# PLC-_-V2.net
KiCad netlist of a schematic drawn in Altium Designer
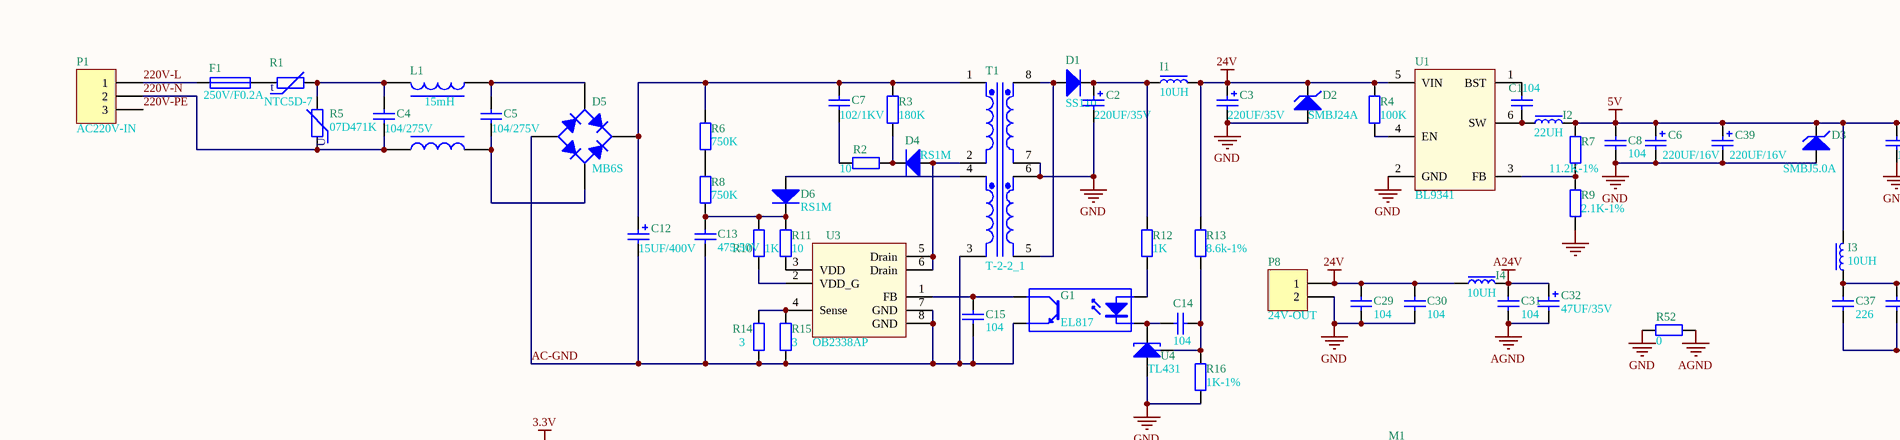
[diagram p0: PLC-无线通讯版-V2.SchDoc, top left]
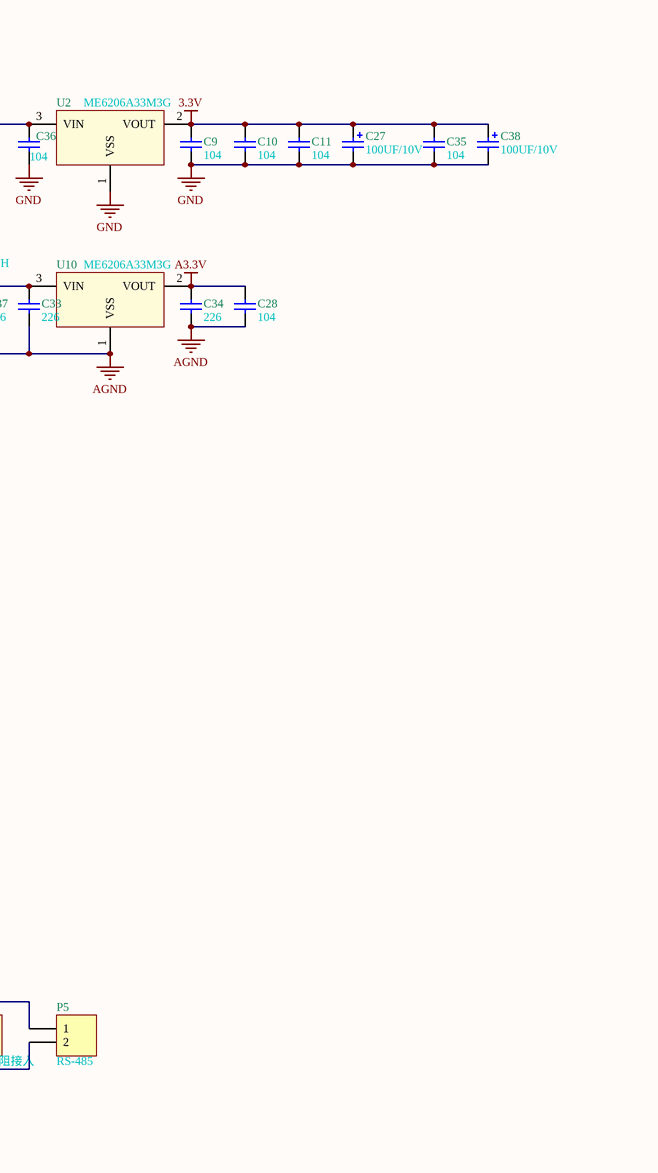
[diagram p1: PLC-无线通讯版-V2.SchDoc, top right]
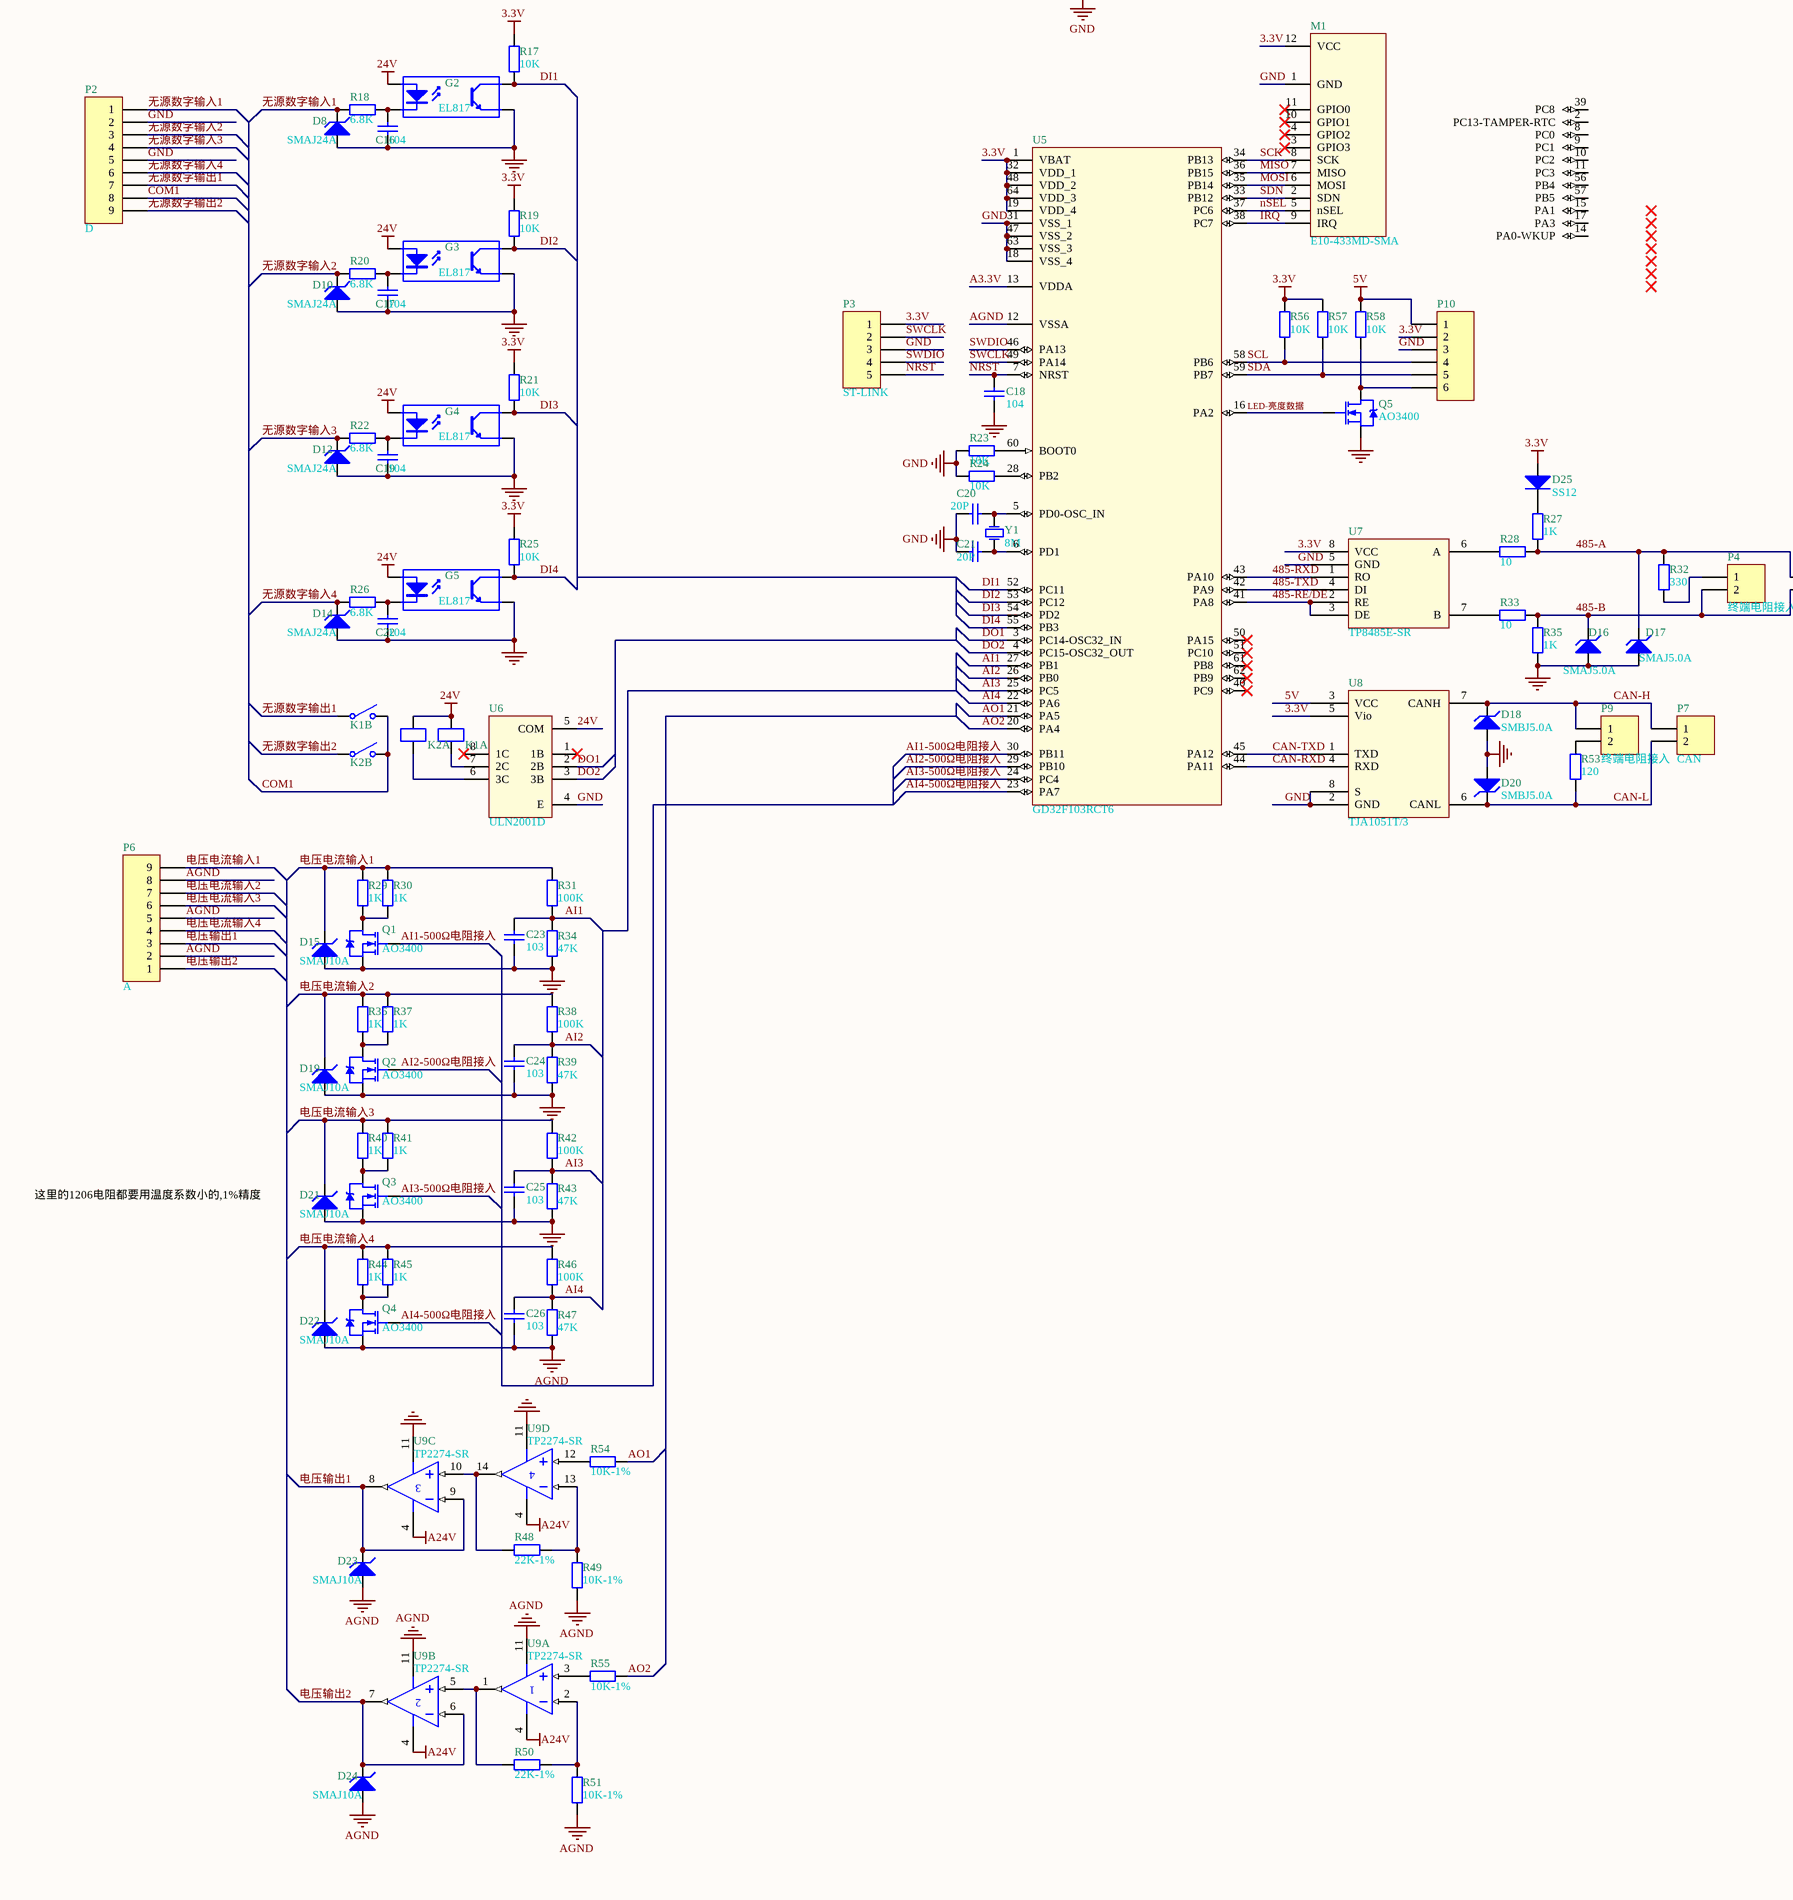
[diagram p2: PLC-无线通讯版-V2.SchDoc, bottom left]
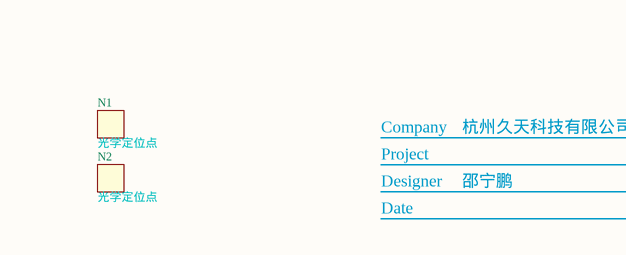
[diagram p3: PLC-无线通讯版-V2.SchDoc, bottom right]

(export (version "E")
  (design (tool "Eeschema 10.0.6"))
  (components
    (comp (ref "C1")
      (value "104")
      (footprint "C-0603")
      (description "Capacitor")
      (fields (field (name "PUBLISHER") "Altium Limited"))
      (libsource (lib "元件2.0") (part "Cap"))
    )
    (comp (ref "C2")
      (value "220UF/35V")
      (footprint "贴片固态电容8*10-M")
      (description "电解电容")
      (fields (field (name "PUBLISHER") "Altium Limited"))
      (libsource (lib "2电容-V1.0") (part "Cap Pol1"))
    )
    (comp (ref "C3")
      (value "220UF/35V")
      (footprint "贴片固态电容8*10-M")
      (description "电解电容")
      (fields (field (name "PUBLISHER") "Altium Limited"))
      (libsource (lib "2电容-V1.0") (part "Cap Pol1"))
    )
    (comp (ref "C4")
      (value "104/275V")
      (footprint "安规电容 脚距10")
      (description "Capacitor")
      (fields (field (name "PUBLISHER") "Altium Limited"))
      (libsource (lib "元件2.0") (part "Cap"))
    )
    (comp (ref "C5")
      (value "104/275V")
      (footprint "安规电容 脚距10")
      (description "Capacitor")
      (fields (field (name "PUBLISHER") "Altium Limited"))
      (libsource (lib "元件2.0") (part "Cap"))
    )
    (comp (ref "C6")
      (value "220UF/16V")
      (footprint "贴片固态电容6.3*7.7")
      (description "Polarized Capacitor (Radial)")
      (fields (field (name "PUBLISHER") "Altium Limited"))
      (libsource (lib "元件2.0") (part "Cap Pol1"))
    )
    (comp (ref "C7")
      (value "102/1KV")
      (footprint "C-1206-M")
      (description "0805")
      (fields (field (name "PUBLISHER") "Altium Limited"))
      (libsource (lib "2电容-V1.0") (part "Cap-0603"))
    )
    (comp (ref "C8")
      (value "104")
      (footprint "C-0603")
      (description "Capacitor")
      (fields (field (name "PUBLISHER") "Altium Limited"))
      (libsource (lib "元件2.0") (part "Cap"))
    )
    (comp (ref "C9")
      (value "104")
      (footprint "C-0603")
      (description "Capacitor")
      (fields (field (name "PUBLISHER") "Altium Limited"))
      (libsource (lib "元件2.0") (part "Cap"))
    )
    (comp (ref "C10")
      (value "104")
      (footprint "C-0603")
      (description "Capacitor")
      (fields (field (name "PUBLISHER") "Altium Limited"))
      (libsource (lib "元件2.0") (part "Cap"))
    )
    (comp (ref "C11")
      (value "104")
      (footprint "C-0603")
      (description "Capacitor")
      (fields (field (name "PUBLISHER") "Altium Limited"))
      (libsource (lib "元件2.0") (part "Cap"))
    )
    (comp (ref "C12")
      (value "15UF/400V")
      (footprint "电解电容10*20蓝色")
      (description "电解电容")
      (fields (field (name "PUBLISHER") "Altium Limited"))
      (libsource (lib "2电容-V1.0") (part "Cap Pol1"))
    )
    (comp (ref "C13")
      (value "475/50V")
      (footprint "C-1206-M")
      (description "Capacitor")
      (fields (field (name "PUBLISHER") "Altium Limited"))
      (libsource (lib "元件2.0") (part "Cap"))
    )
    (comp (ref "C14")
      (value "104")
      (footprint "C-0603")
      (description "Capacitor")
      (fields (field (name "PUBLISHER") "Altium Limited"))
      (libsource (lib "元件2.0") (part "Cap"))
    )
    (comp (ref "C15")
      (value "104")
      (footprint "C-0603")
      (description "Capacitor")
      (fields (field (name "PUBLISHER") "Altium Limited"))
      (libsource (lib "元件2.0") (part "Cap"))
    )
    (comp (ref "C16")
      (value "104")
      (footprint "C-0603")
      (description "0805")
      (fields (field (name "PUBLISHER") "Altium Limited"))
      (libsource (lib "2电容-V1.0") (part "Cap-0603"))
    )
    (comp (ref "C17")
      (value "104")
      (footprint "C-0603")
      (description "0805")
      (fields (field (name "PUBLISHER") "Altium Limited"))
      (libsource (lib "2电容-V1.0") (part "Cap-0603"))
    )
    (comp (ref "C18")
      (value "104")
      (footprint "C-0603")
      (description "0805")
      (fields (field (name "PUBLISHER") "Altium Limited"))
      (libsource (lib "2电容-V1.0") (part "Cap-0603"))
    )
    (comp (ref "C19")
      (value "104")
      (footprint "C-0603")
      (description "0805")
      (fields (field (name "PUBLISHER") "Altium Limited"))
      (libsource (lib "2电容-V1.0") (part "Cap-0603"))
    )
    (comp (ref "C20")
      (value "20P")
      (footprint "C-0603")
      (description "0805")
      (fields (field (name "PUBLISHER") "Altium Limited"))
      (libsource (lib "2电容-V1.0") (part "Cap-0603"))
    )
    (comp (ref "C21")
      (value "20P")
      (footprint "C-0603")
      (description "0805")
      (fields (field (name "PUBLISHER") "Altium Limited"))
      (libsource (lib "2电容-V1.0") (part "Cap-0603"))
    )
    (comp (ref "C22")
      (value "104")
      (footprint "C-0603")
      (description "0805")
      (fields (field (name "PUBLISHER") "Altium Limited"))
      (libsource (lib "2电容-V1.0") (part "Cap-0603"))
    )
    (comp (ref "C23")
      (value "103")
      (footprint "C-0603")
      (description "0805")
      (fields (field (name "PUBLISHER") "Altium Limited"))
      (libsource (lib "2电容-V1.0") (part "Cap-0603"))
    )
    (comp (ref "C24")
      (value "103")
      (footprint "C-0603")
      (description "0805")
      (fields (field (name "PUBLISHER") "Altium Limited"))
      (libsource (lib "2电容-V1.0") (part "Cap-0603"))
    )
    (comp (ref "C25")
      (value "103")
      (footprint "C-0603")
      (description "0805")
      (fields (field (name "PUBLISHER") "Altium Limited"))
      (libsource (lib "2电容-V1.0") (part "Cap-0603"))
    )
    (comp (ref "C26")
      (value "103")
      (footprint "C-0603")
      (description "0805")
      (fields (field (name "PUBLISHER") "Altium Limited"))
      (libsource (lib "2电容-V1.0") (part "Cap-0603"))
    )
    (comp (ref "C27")
      (value "100UF/10V")
      (footprint "贴片固态电容5*5.3")
      (description "Polarized Capacitor (Radial)")
      (fields (field (name "PUBLISHER") "Altium Limited"))
      (libsource (lib "元件2.0") (part "Cap Pol1"))
    )
    (comp (ref "C28")
      (value "104")
      (footprint "C-0603")
      (description "Capacitor")
      (fields (field (name "PUBLISHER") "Altium Limited"))
      (libsource (lib "元件2.0") (part "Cap"))
    )
    (comp (ref "C29")
      (value "104")
      (footprint "C-0603")
      (description "Capacitor")
      (fields (field (name "PUBLISHER") "Altium Limited"))
      (libsource (lib "元件2.0") (part "Cap"))
    )
    (comp (ref "C30")
      (value "104")
      (footprint "C-0603")
      (description "Capacitor")
      (fields (field (name "PUBLISHER") "Altium Limited"))
      (libsource (lib "元件2.0") (part "Cap"))
    )
    (comp (ref "C31")
      (value "104")
      (footprint "C-0603")
      (description "Capacitor")
      (fields (field (name "PUBLISHER") "Altium Limited"))
      (libsource (lib "元件2.0") (part "Cap"))
    )
    (comp (ref "C32")
      (value "47UF/35V")
      (footprint "贴片固态电容6.3*5.3-M")
      (description "Polarized Capacitor (Radial)")
      (fields (field (name "PUBLISHER") "Altium Limited"))
      (libsource (lib "元件2.0") (part "Cap Pol1"))
    )
    (comp (ref "C33")
      (value "226")
      (footprint "C-0805")
      (description "Capacitor")
      (fields (field (name "PUBLISHER") "Altium Limited"))
      (libsource (lib "元件2.0") (part "Cap"))
    )
    (comp (ref "C34")
      (value "226")
      (footprint "C-0805")
      (description "Capacitor")
      (fields (field (name "PUBLISHER") "Altium Limited"))
      (libsource (lib "元件2.0") (part "Cap"))
    )
    (comp (ref "C35")
      (value "104")
      (footprint "C-0603")
      (description "Capacitor")
      (fields (field (name "PUBLISHER") "Altium Limited"))
      (libsource (lib "元件2.0") (part "Cap"))
    )
    (comp (ref "C36")
      (value "104")
      (footprint "C-0603")
      (description "Capacitor")
      (fields (field (name "PUBLISHER") "Altium Limited"))
      (libsource (lib "元件2.0") (part "Cap"))
    )
    (comp (ref "C37")
      (value "226")
      (footprint "C-0805")
      (description "Capacitor")
      (fields (field (name "PUBLISHER") "Altium Limited"))
      (libsource (lib "元件2.0") (part "Cap"))
    )
    (comp (ref "C38")
      (value "100UF/10V")
      (footprint "贴片固态电容5*5.3")
      (description "Polarized Capacitor (Radial)")
      (fields (field (name "PUBLISHER") "Altium Limited"))
      (libsource (lib "元件2.0") (part "Cap Pol1"))
    )
    (comp (ref "C39")
      (value "220UF/16V")
      (footprint "贴片固态电容6.3*7.7")
      (description "Polarized Capacitor (Radial)")
      (fields (field (name "PUBLISHER") "Altium Limited"))
      (libsource (lib "元件2.0") (part "Cap Pol1"))
    )
    (comp (ref "D1")
      (value "SS110")
      (footprint "SMA")
      (description "SMA")
      (libsource (lib "4二极管-V1.1") (part "SS14"))
    )
    (comp (ref "D2")
      (value "SMBJ24A")
      (footprint "SMB-N")
      (description "SMB")
      (libsource (lib "4二极管-V1.1") (part "TVS-1"))
    )
    (comp (ref "D3")
      (value "SMBJ5.0A")
      (footprint "SMB-N")
      (description "SMB")
      (libsource (lib "4二极管-V1.1") (part "TVS-1"))
    )
    (comp (ref "D4")
      (value "RS1M")
      (footprint "SMA")
      (description "SMA")
      (libsource (lib "4二极管-V1.1") (part "SS14"))
    )
    (comp (ref "D5")
      (value "MB6S")
      (footprint "SOIC-4-MBS")
      (description "整流桥堆 MB05S-MB10S")
      (libsource (lib "4二极管-V1.1") (part "MB6S"))
    )
    (comp (ref "D6")
      (value "RS1M")
      (footprint "SMA")
      (description "SMA")
      (libsource (lib "4二极管-V1.1") (part "SS14"))
    )
    (comp (ref "D8")
      (value "SMAJ24A")
      (footprint "SMB-N")
      (description "SMB")
      (libsource (lib "4二极管-V1.1") (part "TVS-1"))
    )
    (comp (ref "D10")
      (value "SMAJ24A")
      (footprint "SMB-N")
      (description "SMB")
      (libsource (lib "4二极管-V1.1") (part "TVS-1"))
    )
    (comp (ref "D12")
      (value "SMAJ24A")
      (footprint "SMB-N")
      (description "SMB")
      (libsource (lib "4二极管-V1.1") (part "TVS-1"))
    )
    (comp (ref "D14")
      (value "SMAJ24A")
      (footprint "SMB-N")
      (description "SMB")
      (libsource (lib "4二极管-V1.1") (part "TVS-1"))
    )
    (comp (ref "D15")
      (value "SMAJ10A")
      (footprint "SMA")
      (description "SMB")
      (libsource (lib "4二极管-V1.1") (part "TVS-1"))
    )
    (comp (ref "D16")
      (value "SMAJ5.0A")
      (footprint "SMB-N")
      (description "SMB")
      (libsource (lib "4二极管-V1.1") (part "TVS-1"))
    )
    (comp (ref "D17")
      (value "SMAJ5.0A")
      (footprint "SMB-N")
      (description "SMB")
      (libsource (lib "4二极管-V1.1") (part "TVS-1"))
    )
    (comp (ref "D18")
      (value "SMBJ5.0A")
      (footprint "SMB-N")
      (description "SMB")
      (libsource (lib "4二极管-V1.1") (part "TVS-1"))
    )
    (comp (ref "D19")
      (value "SMAJ10A")
      (footprint "SMA")
      (description "SMB")
      (libsource (lib "4二极管-V1.1") (part "TVS-1"))
    )
    (comp (ref "D20")
      (value "SMBJ5.0A")
      (footprint "SMB-N")
      (description "SMB")
      (libsource (lib "4二极管-V1.1") (part "TVS-1"))
    )
    (comp (ref "D21")
      (value "SMAJ10A")
      (footprint "SMA")
      (description "SMB")
      (libsource (lib "4二极管-V1.1") (part "TVS-1"))
    )
    (comp (ref "D22")
      (value "SMAJ10A")
      (footprint "SMA")
      (description "SMB")
      (libsource (lib "4二极管-V1.1") (part "TVS-1"))
    )
    (comp (ref "D23")
      (value "SMAJ10A")
      (footprint "SMA")
      (description "SMB")
      (libsource (lib "4二极管-V1.1") (part "TVS-1"))
    )
    (comp (ref "D24")
      (value "SMAJ10A")
      (footprint "SMA")
      (description "SMB")
      (libsource (lib "4二极管-V1.1") (part "TVS-1"))
    )
    (comp (ref "D25")
      (value "SS12")
      (footprint "SMA")
      (description "SMA")
      (libsource (lib "4二极管-V1.1") (part "SS14"))
    )
    (comp (ref "F1")
      (value "250V/F0.2A")
      (footprint "FUSE-3*10带引线")
      (description "Fuse")
      (fields (field (name "PUBLISHER") "Altium Limited"))
      (libsource (lib "11其他元件-V1.0") (part "Fuse 1"))
    )
    (comp (ref "G1")
      (value "EL817")
      (footprint "SOP-4-L")
      (fields (field (name "PUBLISHER") "Altium Limited"))
      (libsource (lib "4二极管-V1.1") (part "EL817"))
    )
    (comp (ref "G2")
      (value "EL817")
      (footprint "SOP-4-L")
      (fields (field (name "PUBLISHER") "Altium Limited"))
      (libsource (lib "4二极管-V1.1") (part "EL817"))
    )
    (comp (ref "G3")
      (value "EL817")
      (footprint "SOP-4-L")
      (fields (field (name "PUBLISHER") "Altium Limited"))
      (libsource (lib "4二极管-V1.1") (part "EL817"))
    )
    (comp (ref "G4")
      (value "EL817")
      (footprint "SOP-4-L")
      (fields (field (name "PUBLISHER") "Altium Limited"))
      (libsource (lib "4二极管-V1.1") (part "EL817"))
    )
    (comp (ref "G5")
      (value "EL817")
      (footprint "SOP-4-L")
      (fields (field (name "PUBLISHER") "Altium Limited"))
      (libsource (lib "4二极管-V1.1") (part "EL817"))
    )
    (comp (ref "I1") (value "10UH") (footprint "CD43-N") (libsource (lib "3电感-V1.0") (part "Inductance3")))
    (comp (ref "I2") (value "22UH") (footprint "CD54") (libsource (lib "3电感-V1.0") (part "Inductance3")))
    (comp (ref "I3") (value "10UH") (footprint "CD43-N") (libsource (lib "3电感-V1.0") (part "Inductance3")))
    (comp (ref "I4") (value "10UH") (footprint "CD43-N") (libsource (lib "3电感-V1.0") (part "Inductance3")))
    (comp (ref "K1")
      (value "HF49FD-D24-1H11")
      (footprint "HF49FD-D24-1H11")
      (libsource (lib "10继电器-V1.0") (part "HF49FD-D24-1H11"))
    )
    (comp (ref "K2")
      (value "HF49FD-D24-1H11")
      (footprint "HF49FD-D24-1H11")
      (libsource (lib "") (part "HF49FD-D24-1H11_1"))
    )
    (comp (ref "L1") (value "15mH") (footprint "UU9.8") (libsource (lib "3电感-V1.0") (part "共模电感UU9.8")))
    (comp (ref "M1")
      (value "E10-433MD-SMA")
      (footprint "E10-433MD-SMA")
      (libsource (lib "6电路模块-V1.0") (part "E10-433MD-SMA"))
    )
    (comp (ref "N1") (value "光学定位点") (footprint "MARK-1mm-3mm") (libsource (lib "11其他元件-V1.0") (part "无引脚")))
    (comp (ref "N2") (value "光学定位点") (footprint "MARK-1mm-3mm") (libsource (lib "11其他元件-V1.0") (part "无引脚")))
    (comp (ref "P1")
      (value "AC220V-IN")
      (footprint "KF2EDGVC-5.08-3P")
      (description "Header, 3-Pin")
      (fields (field (name "PUBLISHER") "Altium Limited"))
      (libsource (lib "5排针-V1.0") (part "Header 3"))
    )
    (comp (ref "P2")
      (value "D")
      (footprint "2EMGKG-5.08-9P")
      (description "Header, 9-Pin")
      (fields (field (name "PUBLISHER") "Altium Limited"))
      (libsource (lib "") (part "Header 9_1"))
    )
    (comp (ref "P3")
      (value "ST-LINK")
      (footprint "5P下载口")
      (description "Header, 5-Pin")
      (fields (field (name "PUBLISHER") "Altium Limited"))
      (libsource (lib "5排针-V1.0") (part "Header 5"))
    )
    (comp (ref "P4")
      (value "终端电阻接入")
      (footprint "HDR1X2")
      (description "Header, 2-Pin")
      (fields (field (name "PUBLISHER") "Altium Limited"))
      (libsource (lib "5排针-V1.0") (part "Header 2"))
    )
    (comp (ref "P5")
      (value "RS-485")
      (footprint "2EMGKG-5.08-2P")
      (description "Header, 2-Pin")
      (fields (field (name "PUBLISHER") "Altium Limited"))
      (libsource (lib "5排针-V1.0") (part "Header 2"))
    )
    (comp (ref "P6")
      (value "A")
      (footprint "2EMGKG-5.08-9P")
      (description "Header, 9-Pin")
      (fields (field (name "PUBLISHER") "Altium Limited"))
      (libsource (lib "5排针-V1.0") (part "Header 9"))
    )
    (comp (ref "P7")
      (value "CAN")
      (footprint "2EMGKG-5.08-2P")
      (description "Header, 2-Pin")
      (fields (field (name "PUBLISHER") "Altium Limited"))
      (libsource (lib "5排针-V1.0") (part "Header 2"))
    )
    (comp (ref "P8")
      (value "24V-OUT")
      (footprint "2EMGKG-5.08-2P")
      (description "Header, 2-Pin")
      (fields (field (name "PUBLISHER") "Altium Limited"))
      (libsource (lib "") (part "Header 2_1"))
    )
    (comp (ref "P9")
      (value "终端电阻接入")
      (footprint "HDR1X2")
      (description "Header, 2-Pin")
      (fields (field (name "PUBLISHER") "Altium Limited"))
      (libsource (lib "5排针-V1.0") (part "Header 2"))
    )
    (comp (ref "P10")
      (value "~")
      (footprint "PH2.0-6A")
      (description "Header, 6-Pin")
      (fields (field (name "PUBLISHER") "Altium Limited"))
      (libsource (lib "5排针-V1.0") (part "Header 6"))
    )
    (comp (ref "Q1")
      (value "AO3400")
      (footprint "SOT-23")
      (description "SOT-23")
      (libsource (lib "4二极管-V1.1") (part "AO3400"))
    )
    (comp (ref "Q2")
      (value "AO3400")
      (footprint "SOT-23")
      (description "SOT-23")
      (libsource (lib "4二极管-V1.1") (part "AO3400"))
    )
    (comp (ref "Q3")
      (value "AO3400")
      (footprint "SOT-23")
      (description "SOT-23")
      (libsource (lib "4二极管-V1.1") (part "AO3400"))
    )
    (comp (ref "Q4")
      (value "AO3400")
      (footprint "SOT-23")
      (description "SOT-23")
      (libsource (lib "4二极管-V1.1") (part "AO3400"))
    )
    (comp (ref "Q5")
      (value "AO3400")
      (footprint "SOT-23")
      (description "SOT-23")
      (libsource (lib "4二极管-V1.1") (part "SI2300"))
    )
    (comp (ref "R1")
      (value "NTC5D-7")
      (footprint "NTC-5D-7")
      (fields (field (name "PUBLISHER") "Altium Limited"))
      (libsource (lib "1电阻-V1.0") (part "热敏电阻"))
    )
    (comp (ref "R2")
      (value "10")
      (footprint "R-0805")
      (description "0603")
      (fields (field (name "PUBLISHER") "Altium Limited"))
      (libsource (lib "") (part "Res2-0603_2"))
    )
    (comp (ref "R3")
      (value "180K")
      (footprint "R-1206-M")
      (description "0603")
      (fields (field (name "PUBLISHER") "Altium Limited"))
      (libsource (lib "") (part "Res2-0603_1"))
    )
    (comp (ref "R4")
      (value "100K")
      (footprint "R-0603")
      (description "0603")
      (fields (field (name "PUBLISHER") "Altium Limited"))
      (libsource (lib "1电阻-V1.0") (part "Res2-0603"))
    )
    (comp (ref "R5") (value "07D471K") (footprint "MOV-07D") (libsource (lib "1电阻-V1.0") (part "压敏电阻")))
    (comp (ref "R6")
      (value "750K")
      (footprint "R-1206-M")
      (description "1%")
      (fields (field (name "PUBLISHER") "Altium Limited"))
      (libsource (lib "") (part "Res2_2"))
    )
    (comp (ref "R7")
      (value "11.2K-1%")
      (footprint "R-0603")
      (description "0603")
      (fields (field (name "PUBLISHER") "Altium Limited"))
      (libsource (lib "1电阻-V1.0") (part "Res2-0603"))
    )
    (comp (ref "R8")
      (value "750K")
      (footprint "R-1206-M")
      (description "1%")
      (fields (field (name "PUBLISHER") "Altium Limited"))
      (libsource (lib "") (part "Res2_2"))
    )
    (comp (ref "R9")
      (value "2.1K-1%")
      (footprint "R-0603")
      (description "0603")
      (fields (field (name "PUBLISHER") "Altium Limited"))
      (libsource (lib "1电阻-V1.0") (part "Res2-0603"))
    )
    (comp (ref "R10")
      (value "1K")
      (footprint "R-0603")
      (description "0603")
      (fields (field (name "PUBLISHER") "Altium Limited"))
      (libsource (lib "") (part "Res2-0603_1"))
    )
    (comp (ref "R11")
      (value "10")
      (footprint "R-0603")
      (description "0603")
      (fields (field (name "PUBLISHER") "Altium Limited"))
      (libsource (lib "") (part "Res2-0603_1"))
    )
    (comp (ref "R12")
      (value "1K")
      (footprint "R-0603")
      (description "1%")
      (fields (field (name "PUBLISHER") "Altium Limited"))
      (libsource (lib "元件2.0") (part "Res2"))
    )
    (comp (ref "R13")
      (value "8.6k-1%")
      (footprint "R-0603")
      (description "1%")
      (fields (field (name "PUBLISHER") "Altium Limited"))
      (libsource (lib "元件2.0") (part "Res2"))
    )
    (comp (ref "R14")
      (value "3")
      (footprint "R-1206-M")
      (description "0603")
      (fields (field (name "PUBLISHER") "Altium Limited"))
      (libsource (lib "") (part "Res2-0603_1"))
    )
    (comp (ref "R15")
      (value "3")
      (footprint "R-1206-M")
      (description "0603")
      (fields (field (name "PUBLISHER") "Altium Limited"))
      (libsource (lib "") (part "Res2-0603_1"))
    )
    (comp (ref "R16")
      (value "1K-1%")
      (footprint "R-0603")
      (description "1%")
      (fields (field (name "PUBLISHER") "Altium Limited"))
      (libsource (lib "元件2.0") (part "Res2"))
    )
    (comp (ref "R17")
      (value "10K")
      (footprint "R-0603")
      (description "0603")
      (fields (field (name "PUBLISHER") "Altium Limited"))
      (libsource (lib "") (part "Res2-0603_1"))
    )
    (comp (ref "R18")
      (value "6.8K")
      (footprint "R-0603")
      (description "0603")
      (fields (field (name "PUBLISHER") "Altium Limited"))
      (libsource (lib "") (part "Res2-0603_2"))
    )
    (comp (ref "R19")
      (value "10K")
      (footprint "R-0603")
      (description "0603")
      (fields (field (name "PUBLISHER") "Altium Limited"))
      (libsource (lib "") (part "Res2-0603_1"))
    )
    (comp (ref "R20")
      (value "6.8K")
      (footprint "R-0603")
      (description "0603")
      (fields (field (name "PUBLISHER") "Altium Limited"))
      (libsource (lib "") (part "Res2-0603_2"))
    )
    (comp (ref "R21")
      (value "10K")
      (footprint "R-0603")
      (description "0603")
      (fields (field (name "PUBLISHER") "Altium Limited"))
      (libsource (lib "") (part "Res2-0603_1"))
    )
    (comp (ref "R22")
      (value "6.8K")
      (footprint "R-0603")
      (description "0603")
      (fields (field (name "PUBLISHER") "Altium Limited"))
      (libsource (lib "") (part "Res2-0603_2"))
    )
    (comp (ref "R23")
      (value "10K")
      (footprint "R-0603")
      (description "0603")
      (fields (field (name "PUBLISHER") "Altium Limited"))
      (libsource (lib "1电阻-V1.0") (part "Res2-0603"))
    )
    (comp (ref "R24")
      (value "10K")
      (footprint "R-0603")
      (description "0603")
      (fields (field (name "PUBLISHER") "Altium Limited"))
      (libsource (lib "1电阻-V1.0") (part "Res2-0603"))
    )
    (comp (ref "R25")
      (value "10K")
      (footprint "R-0603")
      (description "0603")
      (fields (field (name "PUBLISHER") "Altium Limited"))
      (libsource (lib "") (part "Res2-0603_1"))
    )
    (comp (ref "R26")
      (value "6.8K")
      (footprint "R-0603")
      (description "0603")
      (fields (field (name "PUBLISHER") "Altium Limited"))
      (libsource (lib "") (part "Res2-0603_2"))
    )
    (comp (ref "R27")
      (value "1K")
      (footprint "R-0603")
      (description "Resistor")
      (fields (field (name "PUBLISHER") "Altium Limited"))
      (libsource (lib "") (part "Res2_1"))
    )
    (comp (ref "R28")
      (value "10")
      (footprint "R-0805-M")
      (description "Resistor")
      (fields (field (name "PUBLISHER") "Altium Limited"))
      (libsource (lib "") (part "Res2_1"))
    )
    (comp (ref "R29")
      (value "1K")
      (footprint "R-1206-M")
      (description "0603")
      (fields (field (name "PUBLISHER") "Altium Limited"))
      (libsource (lib "") (part "Res2-0603_1"))
    )
    (comp (ref "R30")
      (value "1K")
      (footprint "R-1206-M")
      (description "0603")
      (fields (field (name "PUBLISHER") "Altium Limited"))
      (libsource (lib "") (part "Res2-0603_1"))
    )
    (comp (ref "R31")
      (value "100K")
      (footprint "R-1206-M")
      (description "0603")
      (fields (field (name "PUBLISHER") "Altium Limited"))
      (libsource (lib "") (part "Res2-0603_1"))
    )
    (comp (ref "R32")
      (value "330")
      (footprint "R-1206-M")
      (description "Resistor")
      (fields (field (name "PUBLISHER") "Altium Limited"))
      (libsource (lib "Miscellaneous Devices") (part "Res2"))
    )
    (comp (ref "R33")
      (value "10")
      (footprint "R-0805-M")
      (description "Resistor")
      (fields (field (name "PUBLISHER") "Altium Limited"))
      (libsource (lib "") (part "Res2_1"))
    )
    (comp (ref "R34")
      (value "47K")
      (footprint "R-1206-M")
      (description "0603")
      (fields (field (name "PUBLISHER") "Altium Limited"))
      (libsource (lib "") (part "Res2-0603_1"))
    )
    (comp (ref "R35")
      (value "1K")
      (footprint "R-0603")
      (description "Resistor")
      (fields (field (name "PUBLISHER") "Altium Limited"))
      (libsource (lib "") (part "Res2_3"))
    )
    (comp (ref "R36")
      (value "1K")
      (footprint "R-1206-M")
      (description "0603")
      (fields (field (name "PUBLISHER") "Altium Limited"))
      (libsource (lib "") (part "Res2-0603_1"))
    )
    (comp (ref "R37")
      (value "1K")
      (footprint "R-1206-M")
      (description "0603")
      (fields (field (name "PUBLISHER") "Altium Limited"))
      (libsource (lib "") (part "Res2-0603_1"))
    )
    (comp (ref "R38")
      (value "100K")
      (footprint "R-1206-M")
      (description "0603")
      (fields (field (name "PUBLISHER") "Altium Limited"))
      (libsource (lib "") (part "Res2-0603_1"))
    )
    (comp (ref "R39")
      (value "47K")
      (footprint "R-1206-M")
      (description "0603")
      (fields (field (name "PUBLISHER") "Altium Limited"))
      (libsource (lib "") (part "Res2-0603_1"))
    )
    (comp (ref "R40")
      (value "1K")
      (footprint "R-1206-M")
      (description "0603")
      (fields (field (name "PUBLISHER") "Altium Limited"))
      (libsource (lib "") (part "Res2-0603_1"))
    )
    (comp (ref "R41")
      (value "1K")
      (footprint "R-1206-M")
      (description "0603")
      (fields (field (name "PUBLISHER") "Altium Limited"))
      (libsource (lib "") (part "Res2-0603_1"))
    )
    (comp (ref "R42")
      (value "100K")
      (footprint "R-1206-M")
      (description "0603")
      (fields (field (name "PUBLISHER") "Altium Limited"))
      (libsource (lib "") (part "Res2-0603_1"))
    )
    (comp (ref "R43")
      (value "47K")
      (footprint "R-1206-M")
      (description "0603")
      (fields (field (name "PUBLISHER") "Altium Limited"))
      (libsource (lib "") (part "Res2-0603_1"))
    )
    (comp (ref "R44")
      (value "1K")
      (footprint "R-1206-M")
      (description "0603")
      (fields (field (name "PUBLISHER") "Altium Limited"))
      (libsource (lib "") (part "Res2-0603_1"))
    )
    (comp (ref "R45")
      (value "1K")
      (footprint "R-1206-M")
      (description "0603")
      (fields (field (name "PUBLISHER") "Altium Limited"))
      (libsource (lib "") (part "Res2-0603_1"))
    )
    (comp (ref "R46")
      (value "100K")
      (footprint "R-1206-M")
      (description "0603")
      (fields (field (name "PUBLISHER") "Altium Limited"))
      (libsource (lib "") (part "Res2-0603_1"))
    )
    (comp (ref "R47")
      (value "47K")
      (footprint "R-1206-M")
      (description "0603")
      (fields (field (name "PUBLISHER") "Altium Limited"))
      (libsource (lib "") (part "Res2-0603_1"))
    )
    (comp (ref "R48")
      (value "22K-1%")
      (footprint "R-0603")
      (description "0603")
      (fields (field (name "PUBLISHER") "Altium Limited"))
      (libsource (lib "1电阻-V1.0") (part "Res2-0603"))
    )
    (comp (ref "R49")
      (value "10K-1%")
      (footprint "R-0603")
      (description "0603")
      (fields (field (name "PUBLISHER") "Altium Limited"))
      (libsource (lib "") (part "Res2-0603_3"))
    )
    (comp (ref "R50")
      (value "22K-1%")
      (footprint "R-0603")
      (description "0603")
      (fields (field (name "PUBLISHER") "Altium Limited"))
      (libsource (lib "1电阻-V1.0") (part "Res2-0603"))
    )
    (comp (ref "R51")
      (value "10K-1%")
      (footprint "R-0603")
      (description "0603")
      (fields (field (name "PUBLISHER") "Altium Limited"))
      (libsource (lib "") (part "Res2-0603_3"))
    )
    (comp (ref "R52")
      (value "0")
      (footprint "R-0603")
      (description "0603")
      (fields (field (name "PUBLISHER") "Altium Limited"))
      (libsource (lib "") (part "Res2-0603_1"))
    )
    (comp (ref "R53")
      (value "120")
      (footprint "R-1206")
      (description "Resistor")
      (fields (field (name "PUBLISHER") "Altium Limited"))
      (libsource (lib "Miscellaneous Devices") (part "Res2"))
    )
    (comp (ref "R54")
      (value "10K-1%")
      (footprint "R-0603")
      (description "0603")
      (fields (field (name "PUBLISHER") "Altium Limited"))
      (libsource (lib "") (part "Res2-0603_2"))
    )
    (comp (ref "R55")
      (value "10K-1%")
      (footprint "R-0603")
      (description "0603")
      (fields (field (name "PUBLISHER") "Altium Limited"))
      (libsource (lib "") (part "Res2-0603_2"))
    )
    (comp (ref "R56")
      (value "10K")
      (footprint "R-0603")
      (description "0603")
      (fields (field (name "PUBLISHER") "Altium Limited"))
      (libsource (lib "") (part "Res2-0603_1"))
    )
    (comp (ref "R57")
      (value "10K")
      (footprint "R-0603")
      (description "0603")
      (fields (field (name "PUBLISHER") "Altium Limited"))
      (libsource (lib "") (part "Res2-0603_1"))
    )
    (comp (ref "R58")
      (value "10K")
      (footprint "R-0603")
      (description "0603")
      (fields (field (name "PUBLISHER") "Altium Limited"))
      (libsource (lib "") (part "Res2-0603_1"))
    )
    (comp (ref "T1") (value "T-2-2_1") (footprint "EE19-卧式") (libsource (lib "3电感-V1.0") (part "T-2-2_1")))
    (comp (ref "U1") (value "BL9341") (footprint "SOT-23-6-N") (libsource (lib "电源芯片DC-DC") (part "BL9341")))
    (comp (ref "U2")
      (value "ME6206A33M3G")
      (footprint "SOT-23")
      (description "LDO稳压 SOT-23")
      (libsource (lib "电源芯片-线性稳压-V1") (part "ME6206A33M3G"))
    )
    (comp (ref "U3") (value "OB2338AP") (footprint "DIP8") (libsource (lib "AC-DC控制芯片") (part "OB2338AP")))
    (comp (ref "U4")
      (value "TL431")
      (footprint "SOT-23")
      (description "稳压芯片 SOT-23")
      (libsource (lib "电源芯片-线性稳压-V1") (part "TL431"))
    )
    (comp (ref "U5")
      (value "GD32F103RCT6")
      (footprint "LQFP64-M")
      (libsource (lib "9单片机-V1.0") (part "STM32F103RBT6"))
    )
    (comp (ref "U6")
      (value "ULN2001D")
      (footprint "SOP-8-N")
      (libsource (lib "8集成电路-V1.1") (part "ULN2001D"))
    )
    (comp (ref "U7")
      (value "TP8485E-SR")
      (footprint "SOP-8-N")
      (description "RS485总线转串口")
      (libsource (lib "集成电路1.0") (part "MAX3082"))
    )
    (comp (ref "U8") (value "TJA1051T/3") (footprint "SOP-8-N") (libsource (lib "通讯-V1") (part "TJA1051T/3")))
    (comp (ref "U9")
      (value "TP2274-SR")
      (footprint "SOP-14-M")
      (description "四运放-SOP-14")
      (libsource (lib "8集成电路-V1.1") (part "MCP6004"))
    )
    (comp (ref "U10")
      (value "ME6206A33M3G")
      (footprint "SOT-23")
      (description "LDO稳压 SOT-23")
      (libsource (lib "电源芯片-线性稳压-V1") (part "ME6206A33M3G"))
    )
    (comp (ref "Y1") (value "8M") (footprint "HC-49SMD") (libsource (lib "11其他元件-V1.0") (part "晶振")))
  )
  (nets
    (net (code "1") (name "/220V-L") (class "Default")
      (node (ref "F1") (pin "1") (pinfunction "1_1") (pintype "passive"))
      (node (ref "P1") (pin "1") (pinfunction "1_1") (pintype "passive"))
    )
    (net (code "2") (name "/220V-N") (class "Default")
      (node (ref "C4") (pin "2") (pinfunction "2_2") (pintype "passive"))
      (node (ref "L1") (pin "1") (pinfunction "1_1") (pintype "passive"))
      (node (ref "P1") (pin "2") (pinfunction "2_2") (pintype "passive"))
      (node (ref "R5") (pin "1") (pinfunction "1_1") (pintype "passive"))
    )
    (net (code "3") (name "/220V-PE") (class "Default")
      (node (ref "P1") (pin "3") (pinfunction "3_3") (pintype "passive"))
    )
    (net (code "4") (name "/485-A") (class "Default")
      (node (ref "D17") (pin "2") (pinfunction "K_2") (pintype "passive"))
      (node (ref "P5") (pin "1") (pinfunction "1_1") (pintype "passive"))
      (node (ref "R27") (pin "2") (pinfunction "2_2") (pintype "passive"))
      (node (ref "R28") (pin "1") (pinfunction "1_1") (pintype "passive"))
      (node (ref "R32") (pin "1") (pinfunction "1_1") (pintype "passive"))
    )
    (net (code "5") (name "/485-B") (class "Default")
      (node (ref "D16") (pin "2") (pinfunction "K_2") (pintype "passive"))
      (node (ref "P4") (pin "2") (pinfunction "2_2") (pintype "passive"))
      (node (ref "P5") (pin "2") (pinfunction "2_2") (pintype "passive"))
      (node (ref "R33") (pin "1") (pinfunction "1_1") (pintype "passive"))
      (node (ref "R35") (pin "2") (pinfunction "2_2") (pintype "passive"))
    )
    (net (code "6") (name "/485-RE{slash}DE") (class "Default")
      (node (ref "U5") (pin "41") (pinfunction "PA8_41") (pintype "bidirectional"))
      (node (ref "U7") (pin "2") (pinfunction "RE_2") (pintype "passive"))
      (node (ref "U7") (pin "3") (pinfunction "DE_3") (pintype "passive"))
    )
    (net (code "7") (name "/485-RXD") (class "Default")
      (node (ref "U5") (pin "43") (pinfunction "PA10_43") (pintype "bidirectional"))
      (node (ref "U7") (pin "1") (pinfunction "RO_1") (pintype "passive"))
    )
    (net (code "8") (name "/485-TXD") (class "Default")
      (node (ref "U5") (pin "42") (pinfunction "PA9_42") (pintype "bidirectional"))
      (node (ref "U7") (pin "4") (pinfunction "DI_4") (pintype "passive"))
    )
    (net (code "9") (name "/AC-GND") (class "Default")
      (node (ref "C12") (pin "2") (pinfunction "2_2") (pintype "passive"))
      (node (ref "C13") (pin "1") (pinfunction "1_1") (pintype "passive"))
      (node (ref "C15") (pin "1") (pinfunction "1_1") (pintype "passive"))
      (node (ref "D5") (pin "4") (pinfunction "A_4") (pintype "passive"))
      (node (ref "G1") (pin "3") (pinfunction "E_3") (pintype "passive"))
      (node (ref "R14") (pin "1") (pinfunction "1_1") (pintype "passive"))
      (node (ref "R15") (pin "1") (pinfunction "1_1") (pintype "passive"))
      (node (ref "T1") (pin "3") (pinfunction "3_3") (pintype "passive"))
      (node (ref "U3") (pin "7") (pinfunction "GND_7") (pintype "passive"))
      (node (ref "U3") (pin "8") (pinfunction "GND_8") (pintype "passive"))
    )
    (net (code "10") (name "/AI1") (class "Default")
      (node (ref "C23") (pin "2") (pinfunction "2_2") (pintype "passive"))
      (node (ref "R31") (pin "1") (pinfunction "1_1") (pintype "passive"))
      (node (ref "R34") (pin "2") (pinfunction "2_2") (pintype "passive"))
      (node (ref "U5") (pin "27") (pinfunction "PB1_27") (pintype "bidirectional"))
    )
    (net (code "11") (name "/AI1-500Ω电阻接入") (class "Default")
      (node (ref "Q1") (pin "1") (pinfunction "G_1") (pintype "passive"))
      (node (ref "U5") (pin "30") (pinfunction "PB11_30") (pintype "bidirectional"))
    )
    (net (code "12") (name "/AI2") (class "Default")
      (node (ref "C24") (pin "2") (pinfunction "2_2") (pintype "passive"))
      (node (ref "R38") (pin "1") (pinfunction "1_1") (pintype "passive"))
      (node (ref "R39") (pin "2") (pinfunction "2_2") (pintype "passive"))
      (node (ref "U5") (pin "26") (pinfunction "PB0_26") (pintype "bidirectional"))
    )
    (net (code "13") (name "/AI2-500Ω电阻接入") (class "Default")
      (node (ref "Q2") (pin "1") (pinfunction "G_1") (pintype "passive"))
      (node (ref "U5") (pin "29") (pinfunction "PB10_29") (pintype "bidirectional"))
    )
    (net (code "14") (name "/AI3") (class "Default")
      (node (ref "C25") (pin "2") (pinfunction "2_2") (pintype "passive"))
      (node (ref "R42") (pin "1") (pinfunction "1_1") (pintype "passive"))
      (node (ref "R43") (pin "2") (pinfunction "2_2") (pintype "passive"))
      (node (ref "U5") (pin "25") (pinfunction "PC5_25") (pintype "bidirectional"))
    )
    (net (code "15") (name "/AI3-500Ω电阻接入") (class "Default")
      (node (ref "Q3") (pin "1") (pinfunction "G_1") (pintype "passive"))
      (node (ref "U5") (pin "24") (pinfunction "PC4_24") (pintype "bidirectional"))
    )
    (net (code "16") (name "/AI4") (class "Default")
      (node (ref "C26") (pin "2") (pinfunction "2_2") (pintype "passive"))
      (node (ref "R46") (pin "1") (pinfunction "1_1") (pintype "passive"))
      (node (ref "R47") (pin "2") (pinfunction "2_2") (pintype "passive"))
      (node (ref "U5") (pin "22") (pinfunction "PA6_22") (pintype "bidirectional"))
    )
    (net (code "17") (name "/AI4-500Ω电阻接入") (class "Default")
      (node (ref "Q4") (pin "1") (pinfunction "G_1") (pintype "passive"))
      (node (ref "U5") (pin "23") (pinfunction "PA7_23") (pintype "bidirectional"))
    )
    (net (code "18") (name "/AO1") (class "Default")
      (node (ref "R54") (pin "2") (pinfunction "2_2") (pintype "passive"))
      (node (ref "U5") (pin "21") (pinfunction "PA5_21") (pintype "bidirectional"))
    )
    (net (code "19") (name "/AO2") (class "Default")
      (node (ref "R55") (pin "2") (pinfunction "2_2") (pintype "passive"))
      (node (ref "U5") (pin "20") (pinfunction "PA4_20") (pintype "bidirectional"))
    )
    (net (code "20") (name "/CAN-H") (class "Default")
      (node (ref "D18") (pin "2") (pinfunction "K_2") (pintype "passive"))
      (node (ref "P7") (pin "1") (pinfunction "1_1") (pintype "passive"))
      (node (ref "P9") (pin "1") (pinfunction "1_1") (pintype "passive"))
      (node (ref "U8") (pin "7") (pinfunction "CANH_7") (pintype "passive"))
    )
    (net (code "21") (name "/CAN-L") (class "Default")
      (node (ref "D20") (pin "2") (pinfunction "K_2") (pintype "passive"))
      (node (ref "P7") (pin "2") (pinfunction "2_2") (pintype "passive"))
      (node (ref "R53") (pin "2") (pinfunction "2_2") (pintype "passive"))
      (node (ref "U8") (pin "6") (pinfunction "CANL_6") (pintype "passive"))
    )
    (net (code "22") (name "/CAN-RXD") (class "Default")
      (node (ref "U5") (pin "44") (pinfunction "PA11_44") (pintype "bidirectional"))
      (node (ref "U8") (pin "4") (pinfunction "RXD_4") (pintype "passive"))
    )
    (net (code "23") (name "/CAN-TXD") (class "Default")
      (node (ref "U5") (pin "45") (pinfunction "PA12_45") (pintype "bidirectional"))
      (node (ref "U8") (pin "1") (pinfunction "TXD_1") (pintype "passive"))
    )
    (net (code "24") (name "/COM1") (class "Default")
      (node (ref "K1") (pin "4") (pinfunction "4_4") (pintype "passive"))
      (node (ref "K2") (pin "4") (pinfunction "4_4") (pintype "passive"))
      (node (ref "P2") (pin "8") (pinfunction "8_8") (pintype "passive"))
    )
    (net (code "25") (name "/DI1") (class "Default")
      (node (ref "G2") (pin "4") (pinfunction "C_4") (pintype "passive"))
      (node (ref "R17") (pin "1") (pinfunction "1_1") (pintype "passive"))
      (node (ref "U5") (pin "52") (pinfunction "PC11_52") (pintype "bidirectional"))
    )
    (net (code "26") (name "/DI2") (class "Default")
      (node (ref "G3") (pin "4") (pinfunction "C_4") (pintype "passive"))
      (node (ref "R19") (pin "1") (pinfunction "1_1") (pintype "passive"))
      (node (ref "U5") (pin "53") (pinfunction "PC12_53") (pintype "bidirectional"))
    )
    (net (code "27") (name "/DI3") (class "Default")
      (node (ref "G4") (pin "4") (pinfunction "C_4") (pintype "passive"))
      (node (ref "R21") (pin "1") (pinfunction "1_1") (pintype "passive"))
      (node (ref "U5") (pin "54") (pinfunction "PD2_54") (pintype "bidirectional"))
    )
    (net (code "28") (name "/DI4") (class "Default")
      (node (ref "G5") (pin "4") (pinfunction "C_4") (pintype "passive"))
      (node (ref "R25") (pin "1") (pinfunction "1_1") (pintype "passive"))
      (node (ref "U5") (pin "55") (pinfunction "PB3_55") (pintype "bidirectional"))
    )
    (net (code "29") (name "/DO1") (class "Default")
      (node (ref "U5") (pin "3") (pinfunction "PC14-OSC32_IN_3") (pintype "bidirectional"))
      (node (ref "U6") (pin "2") (pinfunction "2B_2") (pintype "passive"))
    )
    (net (code "30") (name "/DO2") (class "Default")
      (node (ref "U5") (pin "4") (pinfunction "PC15-OSC32_OUT_4") (pintype "bidirectional"))
      (node (ref "U6") (pin "3") (pinfunction "3B_3") (pintype "passive"))
    )
    (net (code "31") (name "/IRQ") (class "Default")
      (node (ref "M1") (pin "9") (pinfunction "IRQ_9") (pintype "passive"))
      (node (ref "U5") (pin "38") (pinfunction "PC7_38") (pintype "bidirectional"))
    )
    (net (code "32") (name "/LED-亮度数据") (class "Default")
      (node (ref "Q5") (pin "1") (pinfunction "G_1") (pintype "passive"))
      (node (ref "U5") (pin "16") (pinfunction "PA2_16") (pintype "bidirectional"))
    )
    (net (code "33") (name "/MISO") (class "Default")
      (node (ref "M1") (pin "7") (pinfunction "MISO_7") (pintype "passive"))
      (node (ref "U5") (pin "36") (pinfunction "PB15_36") (pintype "bidirectional"))
    )
    (net (code "34") (name "/MOSI") (class "Default")
      (node (ref "M1") (pin "6") (pinfunction "MOSI_6") (pintype "passive"))
      (node (ref "U5") (pin "35") (pinfunction "PB14_35") (pintype "bidirectional"))
    )
    (net (code "35") (name "/NRST") (class "Default")
      (node (ref "C18") (pin "2") (pinfunction "2_2") (pintype "passive"))
      (node (ref "P3") (pin "5") (pinfunction "5_5") (pintype "passive"))
      (node (ref "U5") (pin "7") (pinfunction "NRST_7") (pintype "bidirectional"))
    )
    (net (code "36") (name "/SCK") (class "Default")
      (node (ref "M1") (pin "8") (pinfunction "SCK_8") (pintype "passive"))
      (node (ref "U5") (pin "34") (pinfunction "PB13_34") (pintype "bidirectional"))
    )
    (net (code "37") (name "/SCL") (class "Default")
      (node (ref "P10") (pin "4") (pinfunction "4_4") (pintype "passive"))
      (node (ref "R56") (pin "1") (pinfunction "1_1") (pintype "passive"))
      (node (ref "U5") (pin "58") (pinfunction "PB6_58") (pintype "bidirectional"))
    )
    (net (code "38") (name "/SDA") (class "Default")
      (node (ref "P10") (pin "5") (pinfunction "5_5") (pintype "passive"))
      (node (ref "R57") (pin "1") (pinfunction "1_1") (pintype "passive"))
      (node (ref "U5") (pin "59") (pinfunction "PB7_59") (pintype "bidirectional"))
    )
    (net (code "39") (name "/SDN") (class "Default")
      (node (ref "M1") (pin "2") (pinfunction "SDN_2") (pintype "passive"))
      (node (ref "U5") (pin "33") (pinfunction "PB12_33") (pintype "bidirectional"))
    )
    (net (code "40") (name "/SWCLK") (class "Default")
      (node (ref "P3") (pin "2") (pinfunction "2_2") (pintype "passive"))
      (node (ref "U5") (pin "49") (pinfunction "PA14_49") (pintype "bidirectional"))
    )
    (net (code "41") (name "/SWDIO") (class "Default")
      (node (ref "P3") (pin "4") (pinfunction "4_4") (pintype "passive"))
      (node (ref "U5") (pin "46") (pinfunction "PA13_46") (pintype "bidirectional"))
    )
    (net (code "42") (name "/nSEL") (class "Default")
      (node (ref "M1") (pin "5") (pinfunction "nSEL_5") (pintype "passive"))
      (node (ref "U5") (pin "37") (pinfunction "PC6_37") (pintype "bidirectional"))
    )
    (net (code "43") (name "/无源数字输入1") (class "Default")
      (node (ref "D8") (pin "2") (pinfunction "K_2") (pintype "passive"))
      (node (ref "P2") (pin "1") (pinfunction "1_1") (pintype "passive"))
      (node (ref "R18") (pin "1") (pinfunction "1_1") (pintype "passive"))
    )
    (net (code "44") (name "/无源数字输入2") (class "Default")
      (node (ref "D10") (pin "2") (pinfunction "K_2") (pintype "passive"))
      (node (ref "P2") (pin "3") (pinfunction "3_3") (pintype "passive"))
      (node (ref "R20") (pin "1") (pinfunction "1_1") (pintype "passive"))
    )
    (net (code "45") (name "/无源数字输入3") (class "Default")
      (node (ref "D12") (pin "2") (pinfunction "K_2") (pintype "passive"))
      (node (ref "P2") (pin "4") (pinfunction "4_4") (pintype "passive"))
      (node (ref "R22") (pin "1") (pinfunction "1_1") (pintype "passive"))
    )
    (net (code "46") (name "/无源数字输入4") (class "Default")
      (node (ref "D14") (pin "2") (pinfunction "K_2") (pintype "passive"))
      (node (ref "P2") (pin "6") (pinfunction "6_6") (pintype "passive"))
      (node (ref "R26") (pin "1") (pinfunction "1_1") (pintype "passive"))
    )
    (net (code "47") (name "/无源数字输出1") (class "Default")
      (node (ref "K1") (pin "3") (pinfunction "3_3") (pintype "passive"))
      (node (ref "P2") (pin "7") (pinfunction "7_7") (pintype "passive"))
    )
    (net (code "48") (name "/无源数字输出2") (class "Default")
      (node (ref "K2") (pin "3") (pinfunction "3_3") (pintype "passive"))
      (node (ref "P2") (pin "9") (pinfunction "9_9") (pintype "passive"))
    )
    (net (code "49") (name "/电压电流输入1") (class "Default")
      (node (ref "D15") (pin "2") (pinfunction "K_2") (pintype "passive"))
      (node (ref "P6") (pin "9") (pinfunction "9_9") (pintype "passive"))
      (node (ref "R29") (pin "2") (pinfunction "2_2") (pintype "passive"))
      (node (ref "R30") (pin "2") (pinfunction "2_2") (pintype "passive"))
      (node (ref "R31") (pin "2") (pinfunction "2_2") (pintype "passive"))
    )
    (net (code "50") (name "/电压电流输入2") (class "Default")
      (node (ref "D19") (pin "2") (pinfunction "K_2") (pintype "passive"))
      (node (ref "P6") (pin "7") (pinfunction "7_7") (pintype "passive"))
      (node (ref "R36") (pin "2") (pinfunction "2_2") (pintype "passive"))
      (node (ref "R37") (pin "2") (pinfunction "2_2") (pintype "passive"))
      (node (ref "R38") (pin "2") (pinfunction "2_2") (pintype "passive"))
    )
    (net (code "51") (name "/电压电流输入3") (class "Default")
      (node (ref "D21") (pin "2") (pinfunction "K_2") (pintype "passive"))
      (node (ref "P6") (pin "6") (pinfunction "6_6") (pintype "passive"))
      (node (ref "R40") (pin "2") (pinfunction "2_2") (pintype "passive"))
      (node (ref "R41") (pin "2") (pinfunction "2_2") (pintype "passive"))
      (node (ref "R42") (pin "2") (pinfunction "2_2") (pintype "passive"))
    )
    (net (code "52") (name "/电压电流输入4") (class "Default")
      (node (ref "D22") (pin "2") (pinfunction "K_2") (pintype "passive"))
      (node (ref "P6") (pin "4") (pinfunction "4_4") (pintype "passive"))
      (node (ref "R44") (pin "2") (pinfunction "2_2") (pintype "passive"))
      (node (ref "R45") (pin "2") (pinfunction "2_2") (pintype "passive"))
      (node (ref "R46") (pin "2") (pinfunction "2_2") (pintype "passive"))
    )
    (net (code "53") (name "/电压输出1") (class "Default")
      (node (ref "D23") (pin "2") (pinfunction "K_2") (pintype "passive"))
      (node (ref "P6") (pin "3") (pinfunction "3_3") (pintype "passive"))
      (node (ref "U9") (pin "8") (pinfunction "OUT_8") (pintype "output"))
      (node (ref "U9") (pin "9") (pinfunction "IN-_9") (pintype "input"))
    )
    (net (code "54") (name "/电压输出2") (class "Default")
      (node (ref "D24") (pin "2") (pinfunction "K_2") (pintype "passive"))
      (node (ref "P6") (pin "1") (pinfunction "1_1") (pintype "passive"))
      (node (ref "U9") (pin "6") (pinfunction "IN-_6") (pintype "input"))
      (node (ref "U9") (pin "7") (pinfunction "OUT_7") (pintype "output"))
    )
    (net (code "55") (name "3.3V") (class "Default")
      (node (ref "C10") (pin "2") (pinfunction "2_2") (pintype "passive"))
      (node (ref "C11") (pin "2") (pinfunction "2_2") (pintype "passive"))
      (node (ref "C27") (pin "1") (pinfunction "1_1") (pintype "passive"))
      (node (ref "C35") (pin "2") (pinfunction "2_2") (pintype "passive"))
      (node (ref "C38") (pin "1") (pinfunction "1_1") (pintype "passive"))
      (node (ref "C9") (pin "2") (pinfunction "2_2") (pintype "passive"))
      (node (ref "D25") (pin "1") (pinfunction "A_1") (pintype "passive"))
      (node (ref "M1") (pin "12") (pinfunction "VCC_12") (pintype "passive"))
      (node (ref "P10") (pin "2") (pinfunction "2_2") (pintype "passive"))
      (node (ref "P3") (pin "1") (pinfunction "1_1") (pintype "passive"))
      (node (ref "R17") (pin "2") (pinfunction "2_2") (pintype "passive"))
      (node (ref "R19") (pin "2") (pinfunction "2_2") (pintype "passive"))
      (node (ref "R21") (pin "2") (pinfunction "2_2") (pintype "passive"))
      (node (ref "R25") (pin "2") (pinfunction "2_2") (pintype "passive"))
      (node (ref "R56") (pin "2") (pinfunction "2_2") (pintype "passive"))
      (node (ref "R57") (pin "2") (pinfunction "2_2") (pintype "passive"))
      (node (ref "U2") (pin "2") (pinfunction "VOUT_2") (pintype "passive"))
      (node (ref "U5") (pin "1") (pinfunction "VBAT_1") (pintype "power_in"))
      (node (ref "U5") (pin "19") (pinfunction "VDD_4_19") (pintype "power_in"))
      (node (ref "U5") (pin "32") (pinfunction "VDD_1_32") (pintype "power_in"))
      (node (ref "U5") (pin "48") (pinfunction "VDD_2_48") (pintype "power_in"))
      (node (ref "U5") (pin "64") (pinfunction "VDD_3_64") (pintype "power_in"))
      (node (ref "U7") (pin "8") (pinfunction "VCC_8") (pintype "passive"))
      (node (ref "U8") (pin "5") (pinfunction "Vio_5") (pintype "passive"))
    )
    (net (code "56") (name "5V") (class "Default")
      (node (ref "C36") (pin "2") (pinfunction "2_2") (pintype "passive"))
      (node (ref "C39") (pin "1") (pinfunction "1_1") (pintype "passive"))
      (node (ref "C6") (pin "1") (pinfunction "1_1") (pintype "passive"))
      (node (ref "C8") (pin "2") (pinfunction "2_2") (pintype "passive"))
      (node (ref "D3") (pin "2") (pinfunction "K_2") (pintype "passive"))
      (node (ref "I2") (pin "2") (pinfunction "2_2") (pintype "passive"))
      (node (ref "I3") (pin "2") (pinfunction "2_2") (pintype "passive"))
      (node (ref "P10") (pin "1") (pinfunction "1_1") (pintype "passive"))
      (node (ref "R58") (pin "2") (pinfunction "2_2") (pintype "passive"))
      (node (ref "R7") (pin "1") (pinfunction "1_1") (pintype "passive"))
      (node (ref "U2") (pin "3") (pinfunction "VIN_3") (pintype "passive"))
      (node (ref "U8") (pin "3") (pinfunction "VCC_3") (pintype "passive"))
    )
    (net (code "57") (name "24V") (class "Default")
      (node (ref "C29") (pin "2") (pinfunction "2_2") (pintype "passive"))
      (node (ref "C3") (pin "1") (pinfunction "1_1") (pintype "passive"))
      (node (ref "C30") (pin "2") (pinfunction "2_2") (pintype "passive"))
      (node (ref "D2") (pin "2") (pinfunction "K_2") (pintype "passive"))
      (node (ref "G2") (pin "1") (pinfunction "A_1") (pintype "passive"))
      (node (ref "G3") (pin "1") (pinfunction "A_1") (pintype "passive"))
      (node (ref "G4") (pin "1") (pinfunction "A_1") (pintype "passive"))
      (node (ref "G5") (pin "1") (pinfunction "A_1") (pintype "passive"))
      (node (ref "I1") (pin "2") (pinfunction "2_2") (pintype "passive"))
      (node (ref "I4") (pin "1") (pinfunction "1_1") (pintype "passive"))
      (node (ref "K1") (pin "1") (pinfunction "1_1") (pintype "passive"))
      (node (ref "K2") (pin "1") (pinfunction "1_1") (pintype "passive"))
      (node (ref "P8") (pin "1") (pinfunction "1_1") (pintype "passive"))
      (node (ref "R13") (pin "2") (pinfunction "2_2") (pintype "passive"))
      (node (ref "R4") (pin "1") (pinfunction "1_1") (pintype "passive"))
      (node (ref "U1") (pin "5") (pinfunction "VIN_5") (pintype "passive"))
      (node (ref "U6") (pin "5") (pinfunction "COM_5") (pintype "passive"))
    )
    (net (code "58") (name "A3.3V") (class "Default")
      (node (ref "C28") (pin "2") (pinfunction "2_2") (pintype "passive"))
      (node (ref "C34") (pin "2") (pinfunction "2_2") (pintype "passive"))
      (node (ref "U10") (pin "2") (pinfunction "VOUT_2") (pintype "passive"))
      (node (ref "U5") (pin "13") (pinfunction "VDDA_13") (pintype "power_in"))
    )
    (net (code "59") (name "A24V") (class "Default")
      (node (ref "C31") (pin "2") (pinfunction "2_2") (pintype "passive"))
      (node (ref "C32") (pin "1") (pinfunction "1_1") (pintype "passive"))
      (node (ref "I4") (pin "2") (pinfunction "2_2") (pintype "passive"))
      (node (ref "U9") (pin "4") (pinfunction "V+_4") (pintype "power_in"))
    )
    (net (code "60") (name "AGND") (class "Default")
      (node (ref "C23") (pin "1") (pinfunction "1_1") (pintype "passive"))
      (node (ref "C24") (pin "1") (pinfunction "1_1") (pintype "passive"))
      (node (ref "C25") (pin "1") (pinfunction "1_1") (pintype "passive"))
      (node (ref "C26") (pin "1") (pinfunction "1_1") (pintype "passive"))
      (node (ref "C28") (pin "1") (pinfunction "1_1") (pintype "passive"))
      (node (ref "C31") (pin "1") (pinfunction "1_1") (pintype "passive"))
      (node (ref "C32") (pin "2") (pinfunction "2_2") (pintype "passive"))
      (node (ref "C33") (pin "1") (pinfunction "1_1") (pintype "passive"))
      (node (ref "C34") (pin "1") (pinfunction "1_1") (pintype "passive"))
      (node (ref "C37") (pin "1") (pinfunction "1_1") (pintype "passive"))
      (node (ref "D15") (pin "1") (pinfunction "A_1") (pintype "passive"))
      (node (ref "D19") (pin "1") (pinfunction "A_1") (pintype "passive"))
      (node (ref "D21") (pin "1") (pinfunction "A_1") (pintype "passive"))
      (node (ref "D22") (pin "1") (pinfunction "A_1") (pintype "passive"))
      (node (ref "D23") (pin "1") (pinfunction "A_1") (pintype "passive"))
      (node (ref "D24") (pin "1") (pinfunction "A_1") (pintype "passive"))
      (node (ref "P6") (pin "2") (pinfunction "2_2") (pintype "passive"))
      (node (ref "P6") (pin "5") (pinfunction "5_5") (pintype "passive"))
      (node (ref "P6") (pin "8") (pinfunction "8_8") (pintype "passive"))
      (node (ref "Q1") (pin "2") (pinfunction "S_2") (pintype "passive"))
      (node (ref "Q2") (pin "2") (pinfunction "S_2") (pintype "passive"))
      (node (ref "Q3") (pin "2") (pinfunction "S_2") (pintype "passive"))
      (node (ref "Q4") (pin "2") (pinfunction "S_2") (pintype "passive"))
      (node (ref "R34") (pin "1") (pinfunction "1_1") (pintype "passive"))
      (node (ref "R39") (pin "1") (pinfunction "1_1") (pintype "passive"))
      (node (ref "R43") (pin "1") (pinfunction "1_1") (pintype "passive"))
      (node (ref "R47") (pin "1") (pinfunction "1_1") (pintype "passive"))
      (node (ref "R49") (pin "2") (pinfunction "2_2") (pintype "passive"))
      (node (ref "R51") (pin "2") (pinfunction "2_2") (pintype "passive"))
      (node (ref "R52") (pin "2") (pinfunction "2_2") (pintype "passive"))
      (node (ref "U10") (pin "1") (pinfunction "VSS_1") (pintype "passive"))
      (node (ref "U5") (pin "12") (pinfunction "VSSA_12") (pintype "power_in"))
      (node (ref "U9") (pin "11") (pinfunction "V-_11") (pintype "power_in"))
    )
    (net (code "61") (name "GND") (class "Default")
      (node (ref "C10") (pin "1") (pinfunction "1_1") (pintype "passive"))
      (node (ref "C11") (pin "1") (pinfunction "1_1") (pintype "passive"))
      (node (ref "C16") (pin "1") (pinfunction "1_1") (pintype "passive"))
      (node (ref "C17") (pin "1") (pinfunction "1_1") (pintype "passive"))
      (node (ref "C18") (pin "1") (pinfunction "1_1") (pintype "passive"))
      (node (ref "C19") (pin "1") (pinfunction "1_1") (pintype "passive"))
      (node (ref "C2") (pin "2") (pinfunction "2_2") (pintype "passive"))
      (node (ref "C20") (pin "1") (pinfunction "1_1") (pintype "passive"))
      (node (ref "C21") (pin "1") (pinfunction "1_1") (pintype "passive"))
      (node (ref "C22") (pin "1") (pinfunction "1_1") (pintype "passive"))
      (node (ref "C27") (pin "2") (pinfunction "2_2") (pintype "passive"))
      (node (ref "C29") (pin "1") (pinfunction "1_1") (pintype "passive"))
      (node (ref "C3") (pin "2") (pinfunction "2_2") (pintype "passive"))
      (node (ref "C30") (pin "1") (pinfunction "1_1") (pintype "passive"))
      (node (ref "C35") (pin "1") (pinfunction "1_1") (pintype "passive"))
      (node (ref "C36") (pin "1") (pinfunction "1_1") (pintype "passive"))
      (node (ref "C38") (pin "2") (pinfunction "2_2") (pintype "passive"))
      (node (ref "C39") (pin "2") (pinfunction "2_2") (pintype "passive"))
      (node (ref "C6") (pin "2") (pinfunction "2_2") (pintype "passive"))
      (node (ref "C8") (pin "1") (pinfunction "1_1") (pintype "passive"))
      (node (ref "C9") (pin "1") (pinfunction "1_1") (pintype "passive"))
      (node (ref "D10") (pin "1") (pinfunction "A_1") (pintype "passive"))
      (node (ref "D12") (pin "1") (pinfunction "A_1") (pintype "passive"))
      (node (ref "D14") (pin "1") (pinfunction "A_1") (pintype "passive"))
      (node (ref "D16") (pin "1") (pinfunction "A_1") (pintype "passive"))
      (node (ref "D17") (pin "1") (pinfunction "A_1") (pintype "passive"))
      (node (ref "D18") (pin "1") (pinfunction "A_1") (pintype "passive"))
      (node (ref "D2") (pin "1") (pinfunction "A_1") (pintype "passive"))
      (node (ref "D20") (pin "1") (pinfunction "A_1") (pintype "passive"))
      (node (ref "D3") (pin "1") (pinfunction "A_1") (pintype "passive"))
      (node (ref "D8") (pin "1") (pinfunction "A_1") (pintype "passive"))
      (node (ref "G2") (pin "3") (pinfunction "E_3") (pintype "passive"))
      (node (ref "G3") (pin "3") (pinfunction "E_3") (pintype "passive"))
      (node (ref "G4") (pin "3") (pinfunction "E_3") (pintype "passive"))
      (node (ref "G5") (pin "3") (pinfunction "E_3") (pintype "passive"))
      (node (ref "M1") (pin "1") (pinfunction "GND_1") (pintype "passive"))
      (node (ref "P10") (pin "3") (pinfunction "3_3") (pintype "passive"))
      (node (ref "P2") (pin "2") (pinfunction "2_2") (pintype "passive"))
      (node (ref "P2") (pin "5") (pinfunction "5_5") (pintype "passive"))
      (node (ref "P3") (pin "3") (pinfunction "3_3") (pintype "passive"))
      (node (ref "P8") (pin "2") (pinfunction "2_2") (pintype "passive"))
      (node (ref "Q5") (pin "2") (pinfunction "S_2") (pintype "passive"))
      (node (ref "R16") (pin "1") (pinfunction "1_1") (pintype "passive"))
      (node (ref "R23") (pin "2") (pinfunction "2_2") (pintype "passive"))
      (node (ref "R24") (pin "2") (pinfunction "2_2") (pintype "passive"))
      (node (ref "R35") (pin "1") (pinfunction "1_1") (pintype "passive"))
      (node (ref "R52") (pin "1") (pinfunction "1_1") (pintype "passive"))
      (node (ref "R9") (pin "2") (pinfunction "2_2") (pintype "passive"))
      (node (ref "T1") (pin "6") (pinfunction "6_6") (pintype "passive"))
      (node (ref "T1") (pin "7") (pinfunction "7_7") (pintype "passive"))
      (node (ref "U1") (pin "2") (pinfunction "GND_2") (pintype "passive"))
      (node (ref "U2") (pin "1") (pinfunction "VSS_1") (pintype "passive"))
      (node (ref "U4") (pin "3") (pinfunction "A_3") (pintype "passive"))
      (node (ref "U5") (pin "18") (pinfunction "VSS_4_18") (pintype "power_in"))
      (node (ref "U5") (pin "31") (pinfunction "VSS_1_31") (pintype "power_in"))
      (node (ref "U5") (pin "47") (pinfunction "VSS_2_47") (pintype "power_in"))
      (node (ref "U5") (pin "63") (pinfunction "VSS_3_63") (pintype "power_in"))
      (node (ref "U6") (pin "4") (pinfunction "E_4") (pintype "passive"))
      (node (ref "U7") (pin "5") (pinfunction "GND_5") (pintype "passive"))
      (node (ref "U8") (pin "2") (pinfunction "GND_2") (pintype "passive"))
      (node (ref "U8") (pin "8") (pinfunction "S_8") (pintype "passive"))
    )
    (net (code "62") (name "Net-(C4-Pad1)") (class "Default")
      (node (ref "C4") (pin "1") (pinfunction "1_1") (pintype "passive"))
      (node (ref "L1") (pin "4") (pinfunction "4_4") (pintype "passive"))
      (node (ref "R1") (pin "2") (pinfunction "2_2") (pintype "passive"))
      (node (ref "R5") (pin "2") (pinfunction "2_2") (pintype "passive"))
    )
    (net (code "63") (name "Net-(C5-Pad1)") (class "Default")
      (node (ref "C5") (pin "1") (pinfunction "1_1") (pintype "passive"))
      (node (ref "D5") (pin "2") (pinfunction "C_2") (pintype "passive"))
      (node (ref "L1") (pin "3") (pinfunction "3_3") (pintype "passive"))
    )
    (net (code "64") (name "Net-(C5-Pad2)") (class "Default")
      (node (ref "C5") (pin "2") (pinfunction "2_2") (pintype "passive"))
      (node (ref "D5") (pin "1") (pinfunction "C_1") (pintype "passive"))
      (node (ref "L1") (pin "2") (pinfunction "2_2") (pintype "passive"))
    )
    (net (code "65") (name "Net-(C7-Pad1)") (class "Default")
      (node (ref "C7") (pin "1") (pinfunction "1_1") (pintype "passive"))
      (node (ref "R2") (pin "1") (pinfunction "1_1") (pintype "passive"))
    )
    (net (code "66") (name "Net-(D1-A)") (class "Default")
      (node (ref "D1") (pin "1") (pinfunction "A_1") (pintype "passive"))
      (node (ref "T1") (pin "5") (pinfunction "5_5") (pintype "passive"))
      (node (ref "T1") (pin "8") (pinfunction "8_8") (pintype "passive"))
    )
    (net (code "67") (name "Net-(D1-K)") (class "Default")
      (node (ref "C2") (pin "1") (pinfunction "1_1") (pintype "passive"))
      (node (ref "D1") (pin "2") (pinfunction "K_2") (pintype "passive"))
      (node (ref "I1") (pin "1") (pinfunction "1_1") (pintype "passive"))
      (node (ref "R12") (pin "2") (pinfunction "2_2") (pintype "passive"))
    )
    (net (code "68") (name "Net-(D4-A)") (class "Default")
      (node (ref "D4") (pin "1") (pinfunction "A_1") (pintype "passive"))
      (node (ref "T1") (pin "2") (pinfunction "2_2") (pintype "passive"))
      (node (ref "U3") (pin "5") (pinfunction "Drain_5") (pintype "passive"))
      (node (ref "U3") (pin "6") (pinfunction "Drain_6") (pintype "passive"))
    )
    (net (code "69") (name "Net-(D4-K)") (class "Default")
      (node (ref "D4") (pin "2") (pinfunction "K_2") (pintype "passive"))
      (node (ref "R2") (pin "2") (pinfunction "2_2") (pintype "passive"))
      (node (ref "R3") (pin "1") (pinfunction "1_1") (pintype "passive"))
    )
    (net (code "70") (name "Net-(D5-K)") (class "Default")
      (node (ref "C12") (pin "1") (pinfunction "1_1") (pintype "passive"))
      (node (ref "C7") (pin "2") (pinfunction "2_2") (pintype "passive"))
      (node (ref "D5") (pin "3") (pinfunction "K_3") (pintype "passive"))
      (node (ref "R3") (pin "2") (pinfunction "2_2") (pintype "passive"))
      (node (ref "R6") (pin "1") (pinfunction "1_1") (pintype "passive"))
      (node (ref "T1") (pin "1") (pinfunction "1_1") (pintype "passive"))
    )
    (net (code "71") (name "Net-(D6-A)") (class "Default")
      (node (ref "D6") (pin "1") (pinfunction "A_1") (pintype "passive"))
      (node (ref "T1") (pin "4") (pinfunction "4_4") (pintype "passive"))
    )
    (net (code "72") (name "Net-(D6-K)") (class "Default")
      (node (ref "C13") (pin "2") (pinfunction "2_2") (pintype "passive"))
      (node (ref "D6") (pin "2") (pinfunction "K_2") (pintype "passive"))
      (node (ref "R10") (pin "2") (pinfunction "2_2") (pintype "passive"))
      (node (ref "R11") (pin "2") (pinfunction "2_2") (pintype "passive"))
      (node (ref "R8") (pin "2") (pinfunction "2_2") (pintype "passive"))
    )
    (net (code "73") (name "Net-(D25-K)") (class "Default")
      (node (ref "D25") (pin "2") (pinfunction "K_2") (pintype "passive"))
      (node (ref "R27") (pin "1") (pinfunction "1_1") (pintype "passive"))
    )
    (net (code "74") (name "Net-(F1-Pad2)") (class "Default")
      (node (ref "F1") (pin "2") (pinfunction "2_2") (pintype "passive"))
      (node (ref "R1") (pin "1") (pinfunction "1_1") (pintype "passive"))
    )
    (net (code "75") (name "Net-(G1-A)") (class "Default")
      (node (ref "G1") (pin "1") (pinfunction "A_1") (pintype "passive"))
      (node (ref "R12") (pin "1") (pinfunction "1_1") (pintype "passive"))
    )
    (net (code "76") (name "Net-(G1-C)") (class "Default")
      (node (ref "C15") (pin "2") (pinfunction "2_2") (pintype "passive"))
      (node (ref "G1") (pin "4") (pinfunction "C_4") (pintype "passive"))
      (node (ref "U3") (pin "1") (pinfunction "FB_1") (pintype "passive"))
    )
    (net (code "77") (name "Net-(G1-K)") (class "Default")
      (node (ref "C14") (pin "1") (pinfunction "1_1") (pintype "passive"))
      (node (ref "G1") (pin "2") (pinfunction "K_2") (pintype "passive"))
      (node (ref "U4") (pin "2") (pinfunction "K_2") (pintype "passive"))
    )
    (net (code "78") (name "Net-(G2-K)") (class "Default")
      (node (ref "C16") (pin "2") (pinfunction "2_2") (pintype "passive"))
      (node (ref "G2") (pin "2") (pinfunction "K_2") (pintype "passive"))
      (node (ref "R18") (pin "2") (pinfunction "2_2") (pintype "passive"))
    )
    (net (code "79") (name "Net-(G3-K)") (class "Default")
      (node (ref "C17") (pin "2") (pinfunction "2_2") (pintype "passive"))
      (node (ref "G3") (pin "2") (pinfunction "K_2") (pintype "passive"))
      (node (ref "R20") (pin "2") (pinfunction "2_2") (pintype "passive"))
    )
    (net (code "80") (name "Net-(G4-K)") (class "Default")
      (node (ref "C19") (pin "2") (pinfunction "2_2") (pintype "passive"))
      (node (ref "G4") (pin "2") (pinfunction "K_2") (pintype "passive"))
      (node (ref "R22") (pin "2") (pinfunction "2_2") (pintype "passive"))
    )
    (net (code "81") (name "Net-(G5-K)") (class "Default")
      (node (ref "C22") (pin "2") (pinfunction "2_2") (pintype "passive"))
      (node (ref "G5") (pin "2") (pinfunction "K_2") (pintype "passive"))
      (node (ref "R26") (pin "2") (pinfunction "2_2") (pintype "passive"))
    )
    (net (code "82") (name "Net-(P4-Pad1)") (class "Default")
      (node (ref "P4") (pin "1") (pinfunction "1_1") (pintype "passive"))
      (node (ref "R32") (pin "2") (pinfunction "2_2") (pintype "passive"))
    )
    (net (code "83") (name "Net-(P9-Pad2)") (class "Default")
      (node (ref "P9") (pin "2") (pinfunction "2_2") (pintype "passive"))
      (node (ref "R53") (pin "1") (pinfunction "1_1") (pintype "passive"))
    )
    (net (code "84") (name "Net-(Q1-D)") (class "Default")
      (node (ref "Q1") (pin "3") (pinfunction "D_3") (pintype "passive"))
      (node (ref "R29") (pin "1") (pinfunction "1_1") (pintype "passive"))
      (node (ref "R30") (pin "1") (pinfunction "1_1") (pintype "passive"))
    )
    (net (code "85") (name "Net-(Q2-D)") (class "Default")
      (node (ref "Q2") (pin "3") (pinfunction "D_3") (pintype "passive"))
      (node (ref "R36") (pin "1") (pinfunction "1_1") (pintype "passive"))
      (node (ref "R37") (pin "1") (pinfunction "1_1") (pintype "passive"))
    )
    (net (code "86") (name "Net-(Q3-D)") (class "Default")
      (node (ref "Q3") (pin "3") (pinfunction "D_3") (pintype "passive"))
      (node (ref "R40") (pin "1") (pinfunction "1_1") (pintype "passive"))
      (node (ref "R41") (pin "1") (pinfunction "1_1") (pintype "passive"))
    )
    (net (code "87") (name "Net-(Q4-D)") (class "Default")
      (node (ref "Q4") (pin "3") (pinfunction "D_3") (pintype "passive"))
      (node (ref "R44") (pin "1") (pinfunction "1_1") (pintype "passive"))
      (node (ref "R45") (pin "1") (pinfunction "1_1") (pintype "passive"))
    )
    (net (code "88") (name "Net-(Q5-D)") (class "Default")
      (node (ref "P10") (pin "6") (pinfunction "6_6") (pintype "passive"))
      (node (ref "Q5") (pin "3") (pinfunction "D_3") (pintype "passive"))
      (node (ref "R58") (pin "1") (pinfunction "1_1") (pintype "passive"))
    )
    (net (code "89") (name "Net-(R6-Pad2)") (class "Default")
      (node (ref "R6") (pin "2") (pinfunction "2_2") (pintype "passive"))
      (node (ref "R8") (pin "1") (pinfunction "1_1") (pintype "passive"))
    )
    (net (code "90") (name "Net-(U1-BST)") (class "Default")
      (node (ref "C1") (pin "2") (pinfunction "2_2") (pintype "passive"))
      (node (ref "U1") (pin "1") (pinfunction "BST_1") (pintype "passive"))
    )
    (net (code "91") (name "Net-(U1-EN)") (class "Default")
      (node (ref "R4") (pin "2") (pinfunction "2_2") (pintype "passive"))
      (node (ref "U1") (pin "4") (pinfunction "EN_4") (pintype "passive"))
    )
    (net (code "92") (name "Net-(U1-FB)") (class "Default")
      (node (ref "R7") (pin "2") (pinfunction "2_2") (pintype "passive"))
      (node (ref "R9") (pin "1") (pinfunction "1_1") (pintype "passive"))
      (node (ref "U1") (pin "3") (pinfunction "FB_3") (pintype "passive"))
    )
    (net (code "93") (name "Net-(U1-SW)") (class "Default")
      (node (ref "C1") (pin "1") (pinfunction "1_1") (pintype "passive"))
      (node (ref "I2") (pin "1") (pinfunction "1_1") (pintype "passive"))
      (node (ref "U1") (pin "6") (pinfunction "SW_6") (pintype "passive"))
    )
    (net (code "94") (name "Net-(U3-Sense)") (class "Default")
      (node (ref "R14") (pin "2") (pinfunction "2_2") (pintype "passive"))
      (node (ref "R15") (pin "2") (pinfunction "2_2") (pintype "passive"))
      (node (ref "U3") (pin "4") (pinfunction "Sense_4") (pintype "passive"))
    )
    (net (code "95") (name "Net-(U3-VDD)") (class "Default")
      (node (ref "R11") (pin "1") (pinfunction "1_1") (pintype "passive"))
      (node (ref "U3") (pin "3") (pinfunction "VDD_3") (pintype "passive"))
    )
    (net (code "96") (name "Net-(U3-VDD_G)") (class "Default")
      (node (ref "R10") (pin "1") (pinfunction "1_1") (pintype "passive"))
      (node (ref "U3") (pin "2") (pinfunction "VDD_G_2") (pintype "passive"))
    )
    (net (code "97") (name "Net-(U4-REF)") (class "Default")
      (node (ref "C14") (pin "2") (pinfunction "2_2") (pintype "passive"))
      (node (ref "R13") (pin "1") (pinfunction "1_1") (pintype "passive"))
      (node (ref "R16") (pin "2") (pinfunction "2_2") (pintype "passive"))
      (node (ref "U4") (pin "1") (pinfunction "REF_1") (pintype "passive"))
    )
    (net (code "98") (name "Net-(U5-BOOT0)") (class "Default")
      (node (ref "R23") (pin "1") (pinfunction "1_1") (pintype "passive"))
      (node (ref "U5") (pin "60") (pinfunction "BOOT0_60") (pintype "input"))
    )
    (net (code "99") (name "Net-(U5-PB2)") (class "Default")
      (node (ref "R24") (pin "1") (pinfunction "1_1") (pintype "passive"))
      (node (ref "U5") (pin "28") (pinfunction "PB2_28") (pintype "bidirectional"))
    )
    (net (code "100") (name "Net-(U5-PD0-OSC_IN)") (class "Default")
      (node (ref "C20") (pin "2") (pinfunction "2_2") (pintype "passive"))
      (node (ref "U5") (pin "5") (pinfunction "PD0-OSC_IN_5") (pintype "bidirectional"))
      (node (ref "Y1") (pin "2") (pinfunction "OSC2_2") (pintype "passive"))
    )
    (net (code "101") (name "Net-(U5-PD1)") (class "Default")
      (node (ref "C21") (pin "2") (pinfunction "2_2") (pintype "passive"))
      (node (ref "U5") (pin "6") (pinfunction "PD1_6") (pintype "bidirectional"))
      (node (ref "Y1") (pin "1") (pinfunction "OSC1_1") (pintype "passive"))
    )
    (net (code "102") (name "Net-(U6-2C)") (class "Default")
      (node (ref "K1") (pin "2") (pinfunction "2_2") (pintype "passive"))
      (node (ref "U6") (pin "7") (pinfunction "2C_7") (pintype "passive"))
    )
    (net (code "103") (name "Net-(U6-3C)") (class "Default")
      (node (ref "K2") (pin "2") (pinfunction "2_2") (pintype "passive"))
      (node (ref "U6") (pin "6") (pinfunction "3C_6") (pintype "passive"))
    )
    (net (code "104") (name "Net-(U7-A)") (class "Default")
      (node (ref "R28") (pin "2") (pinfunction "2_2") (pintype "passive"))
      (node (ref "U7") (pin "6") (pinfunction "A_6") (pintype "passive"))
    )
    (net (code "105") (name "Net-(U7-B)") (class "Default")
      (node (ref "R33") (pin "2") (pinfunction "2_2") (pintype "passive"))
      (node (ref "U7") (pin "7") (pinfunction "B_7") (pintype "passive"))
    )
    (net (code "106") (name "Net-(U9A-IN+)") (class "Default")
      (node (ref "R55") (pin "1") (pinfunction "1_1") (pintype "passive"))
      (node (ref "U9") (pin "3") (pinfunction "IN+_3") (pintype "input"))
    )
    (net (code "107") (name "Net-(U9A-IN-)") (class "Default")
      (node (ref "R50") (pin "1") (pinfunction "1_1") (pintype "passive"))
      (node (ref "R51") (pin "1") (pinfunction "1_1") (pintype "passive"))
      (node (ref "U9") (pin "2") (pinfunction "IN-_2") (pintype "input"))
    )
    (net (code "108") (name "Net-(U9A-OUT)") (class "Default")
      (node (ref "R50") (pin "2") (pinfunction "2_2") (pintype "passive"))
      (node (ref "U9") (pin "1") (pinfunction "OUT_1") (pintype "output"))
      (node (ref "U9") (pin "5") (pinfunction "IN+_5") (pintype "input"))
    )
    (net (code "109") (name "Net-(U9C-IN+)") (class "Default")
      (node (ref "R48") (pin "2") (pinfunction "2_2") (pintype "passive"))
      (node (ref "U9") (pin "10") (pinfunction "IN+_10") (pintype "input"))
      (node (ref "U9") (pin "14") (pinfunction "OUT_14") (pintype "output"))
    )
    (net (code "110") (name "Net-(U9D-IN+)") (class "Default")
      (node (ref "R54") (pin "1") (pinfunction "1_1") (pintype "passive"))
      (node (ref "U9") (pin "12") (pinfunction "IN+_12") (pintype "input"))
    )
    (net (code "111") (name "Net-(U9D-IN-)") (class "Default")
      (node (ref "R48") (pin "1") (pinfunction "1_1") (pintype "passive"))
      (node (ref "R49") (pin "1") (pinfunction "1_1") (pintype "passive"))
      (node (ref "U9") (pin "13") (pinfunction "IN-_13") (pintype "input"))
    )
    (net (code "112") (name "Net-(U10-VIN)") (class "Default")
      (node (ref "C33") (pin "2") (pinfunction "2_2") (pintype "passive"))
      (node (ref "C37") (pin "2") (pinfunction "2_2") (pintype "passive"))
      (node (ref "I3") (pin "1") (pinfunction "1_1") (pintype "passive"))
      (node (ref "U10") (pin "3") (pinfunction "VIN_3") (pintype "passive"))
    )
    (net (code "113") (name "unconnected-(M1-GPIO0-Pad11)") (class "Default")
      (node (ref "M1") (pin "11") (pinfunction "GPIO0_11") (pintype "passive+no_connect"))
    )
    (net (code "114") (name "unconnected-(M1-GPIO1-Pad10)") (class "Default")
      (node (ref "M1") (pin "10") (pinfunction "GPIO1_10") (pintype "passive+no_connect"))
    )
    (net (code "115") (name "unconnected-(M1-GPIO2-Pad4)") (class "Default")
      (node (ref "M1") (pin "4") (pinfunction "GPIO2_4") (pintype "passive+no_connect"))
    )
    (net (code "116") (name "unconnected-(M1-GPIO3-Pad3)") (class "Default")
      (node (ref "M1") (pin "3") (pinfunction "GPIO3_3") (pintype "passive+no_connect"))
    )
    (net (code "117") (name "unconnected-(U5-PA0-WKUP-Pad14)") (class "Default")
      (node (ref "U5") (pin "14") (pinfunction "PA0-WKUP_14") (pintype "bidirectional"))
    )
    (net (code "118") (name "unconnected-(U5-PA1-Pad15)") (class "Default")
      (node (ref "U5") (pin "15") (pinfunction "PA1_15") (pintype "bidirectional"))
    )
    (net (code "119") (name "unconnected-(U5-PA3-Pad17)") (class "Default")
      (node (ref "U5") (pin "17") (pinfunction "PA3_17") (pintype "bidirectional"))
    )
    (net (code "120") (name "unconnected-(U5-PA15-Pad50)") (class "Default")
      (node (ref "U5") (pin "50") (pinfunction "PA15_50") (pintype "bidirectional+no_connect"))
    )
    (net (code "121") (name "unconnected-(U5-PB4-Pad56)") (class "Default")
      (node (ref "U5") (pin "56") (pinfunction "PB4_56") (pintype "bidirectional"))
    )
    (net (code "122") (name "unconnected-(U5-PB5-Pad57)") (class "Default")
      (node (ref "U5") (pin "57") (pinfunction "PB5_57") (pintype "bidirectional"))
    )
    (net (code "123") (name "unconnected-(U5-PB8-Pad61)") (class "Default")
      (node (ref "U5") (pin "61") (pinfunction "PB8_61") (pintype "bidirectional+no_connect"))
    )
    (net (code "124") (name "unconnected-(U5-PB9-Pad62)") (class "Default")
      (node (ref "U5") (pin "62") (pinfunction "PB9_62") (pintype "bidirectional+no_connect"))
    )
    (net (code "125") (name "unconnected-(U5-PC0-Pad8)") (class "Default")
      (node (ref "U5") (pin "8") (pinfunction "PC0_8") (pintype "bidirectional"))
    )
    (net (code "126") (name "unconnected-(U5-PC1-Pad9)") (class "Default")
      (node (ref "U5") (pin "9") (pinfunction "PC1_9") (pintype "bidirectional"))
    )
    (net (code "127") (name "unconnected-(U5-PC2-Pad10)") (class "Default")
      (node (ref "U5") (pin "10") (pinfunction "PC2_10") (pintype "bidirectional"))
    )
    (net (code "128") (name "unconnected-(U5-PC3-Pad11)") (class "Default")
      (node (ref "U5") (pin "11") (pinfunction "PC3_11") (pintype "bidirectional"))
    )
    (net (code "129") (name "unconnected-(U5-PC8-Pad39)") (class "Default")
      (node (ref "U5") (pin "39") (pinfunction "PC8_39") (pintype "bidirectional"))
    )
    (net (code "130") (name "unconnected-(U5-PC9-Pad40)") (class "Default")
      (node (ref "U5") (pin "40") (pinfunction "PC9_40") (pintype "bidirectional+no_connect"))
    )
    (net (code "131") (name "unconnected-(U5-PC10-Pad51)") (class "Default")
      (node (ref "U5") (pin "51") (pinfunction "PC10_51") (pintype "bidirectional+no_connect"))
    )
    (net (code "132") (name "unconnected-(U5-PC13-TAMPER-RTC-Pad2)") (class "Default")
      (node (ref "U5") (pin "2") (pinfunction "PC13-TAMPER-RTC_2") (pintype "bidirectional"))
    )
    (net (code "133") (name "unconnected-(U6-1B-Pad1)") (class "Default")
      (node (ref "U6") (pin "1") (pinfunction "1B_1") (pintype "passive+no_connect"))
    )
    (net (code "134") (name "unconnected-(U6-1C-Pad8)") (class "Default")
      (node (ref "U6") (pin "8") (pinfunction "1C_8") (pintype "passive+no_connect"))
    )
  )
)
